# Inverter_New.net
KiCad netlist of a schematic drawn in EAGLE
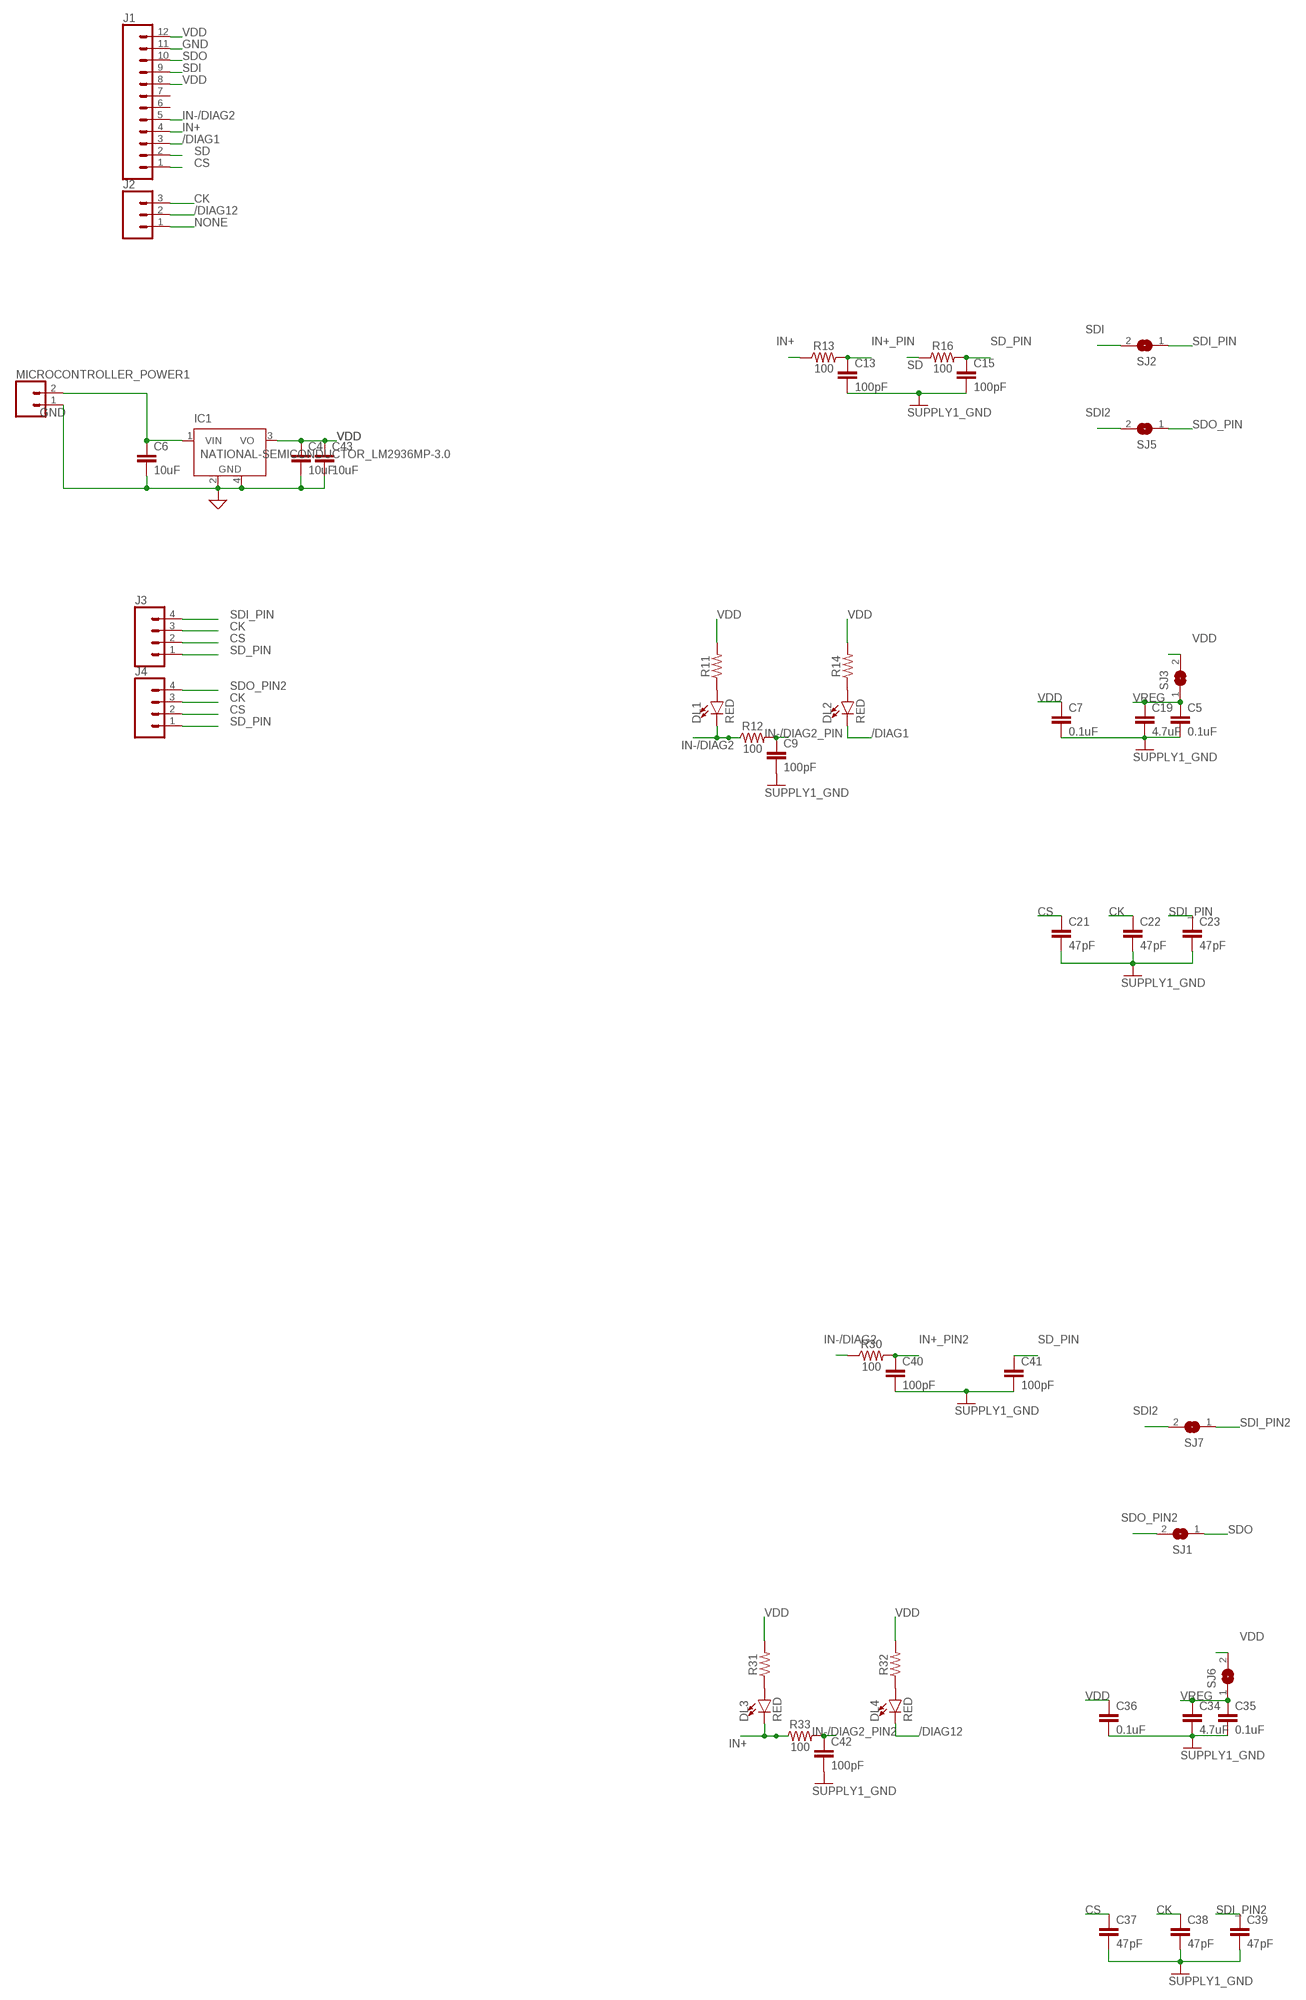
[diagram p0: schematic, sheet 1, part 1 of 2]
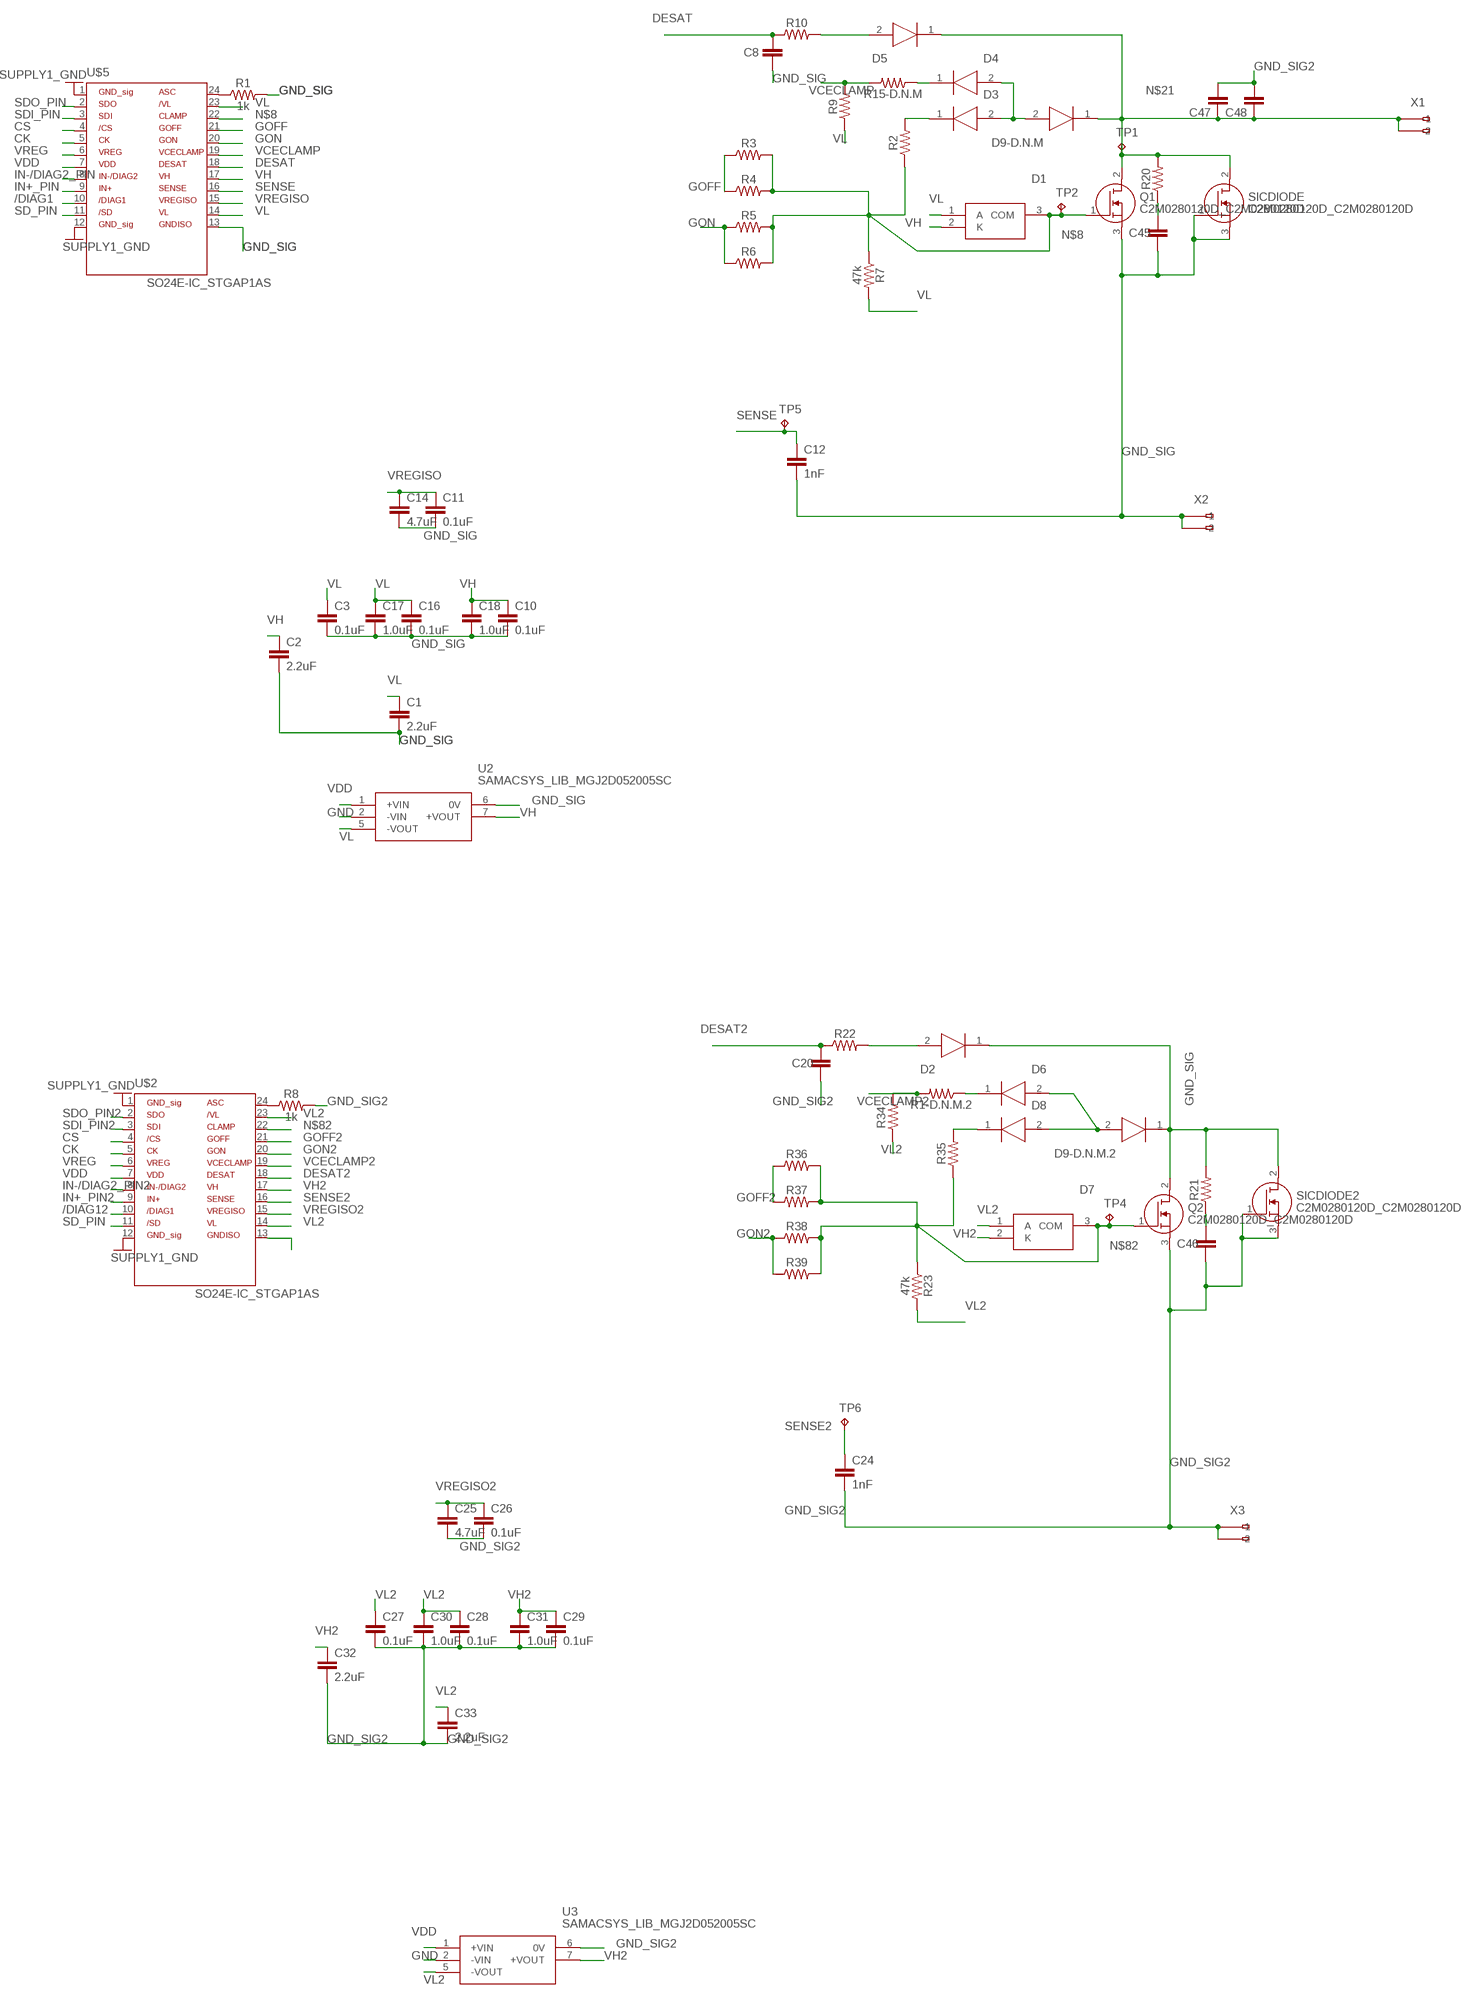
[diagram p1: schematic, sheet 1, part 2 of 2]
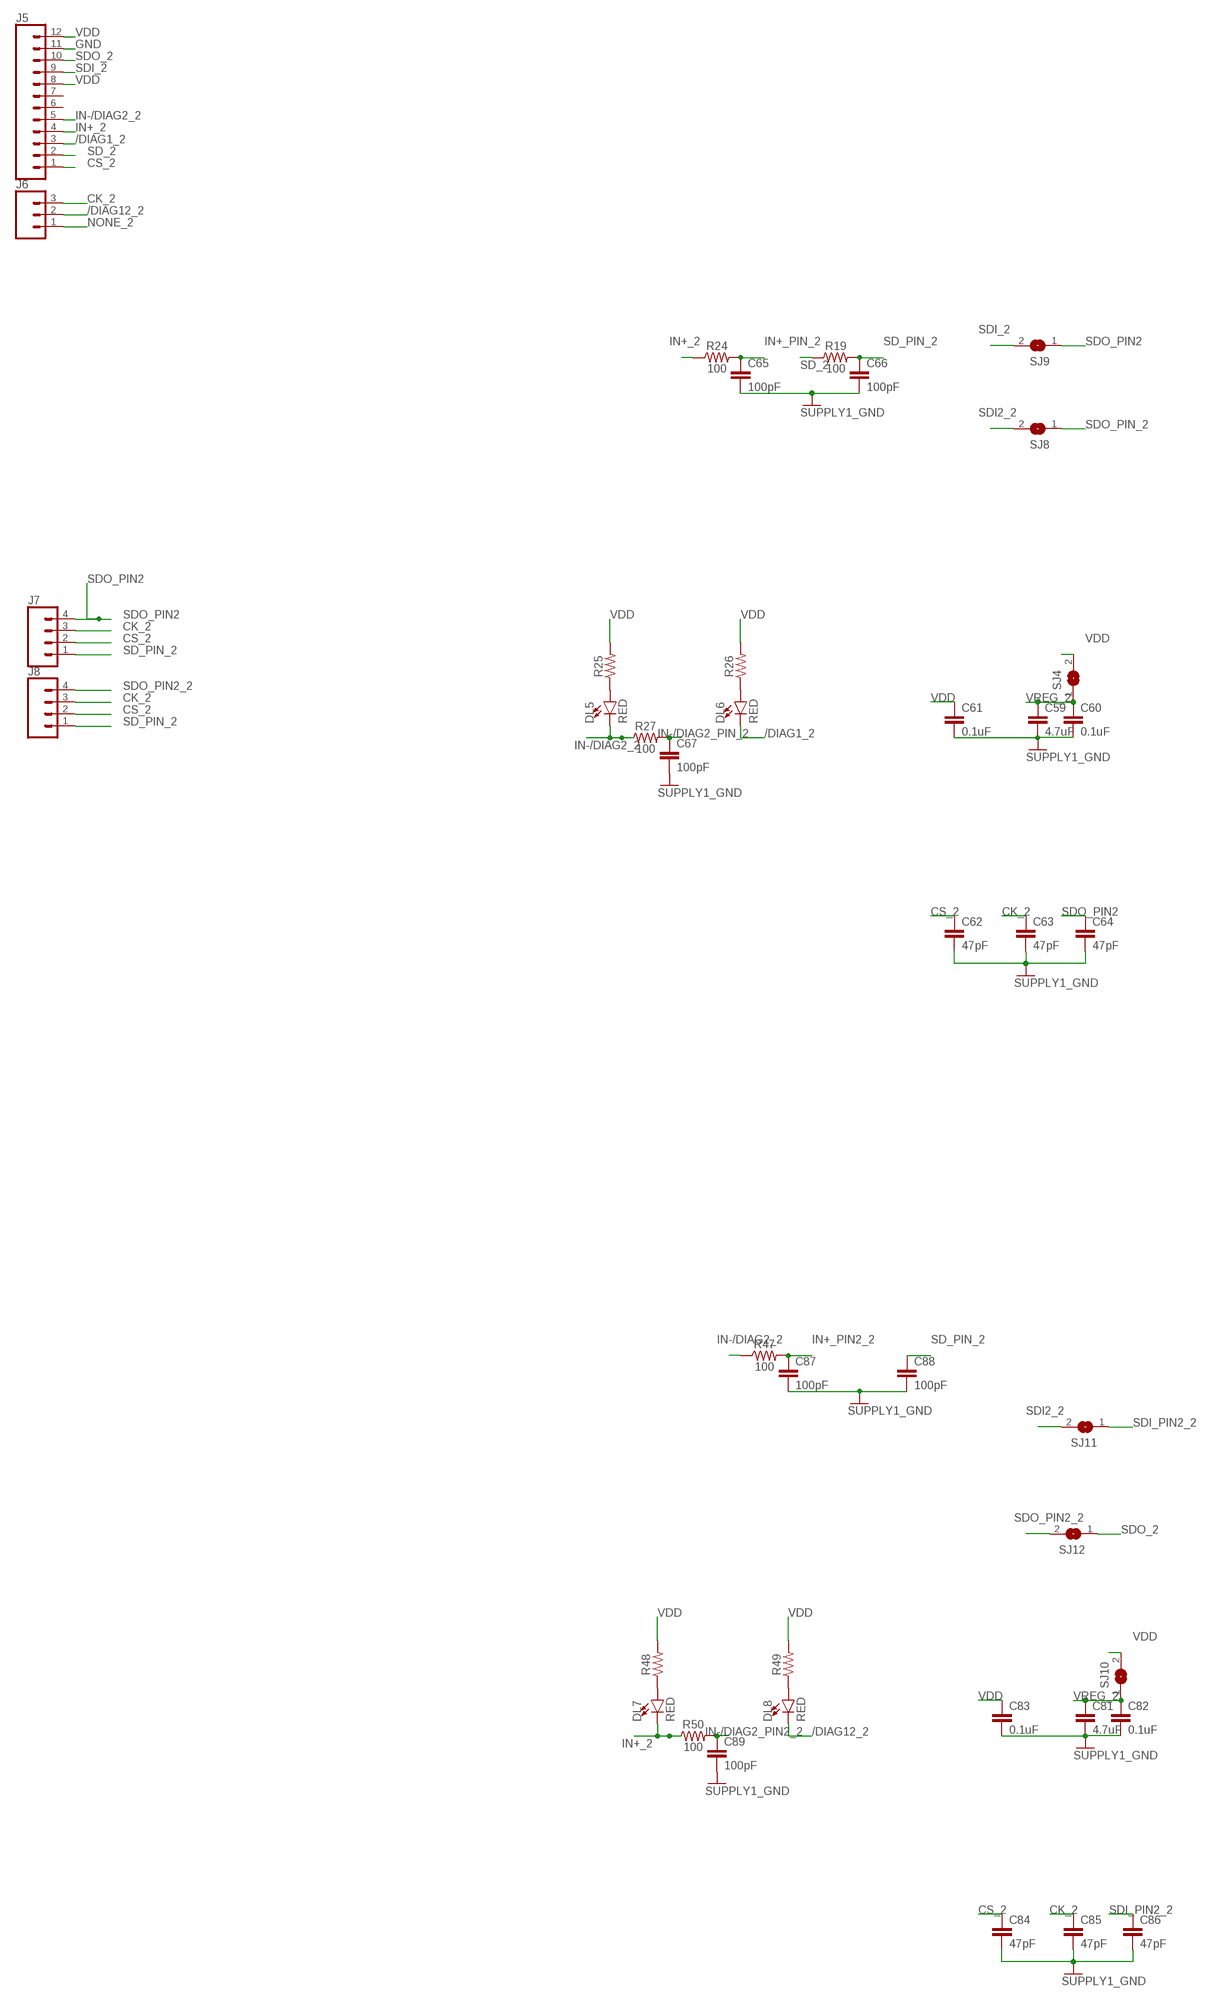
[diagram p2: schematic, sheet 2, part 1 of 2]
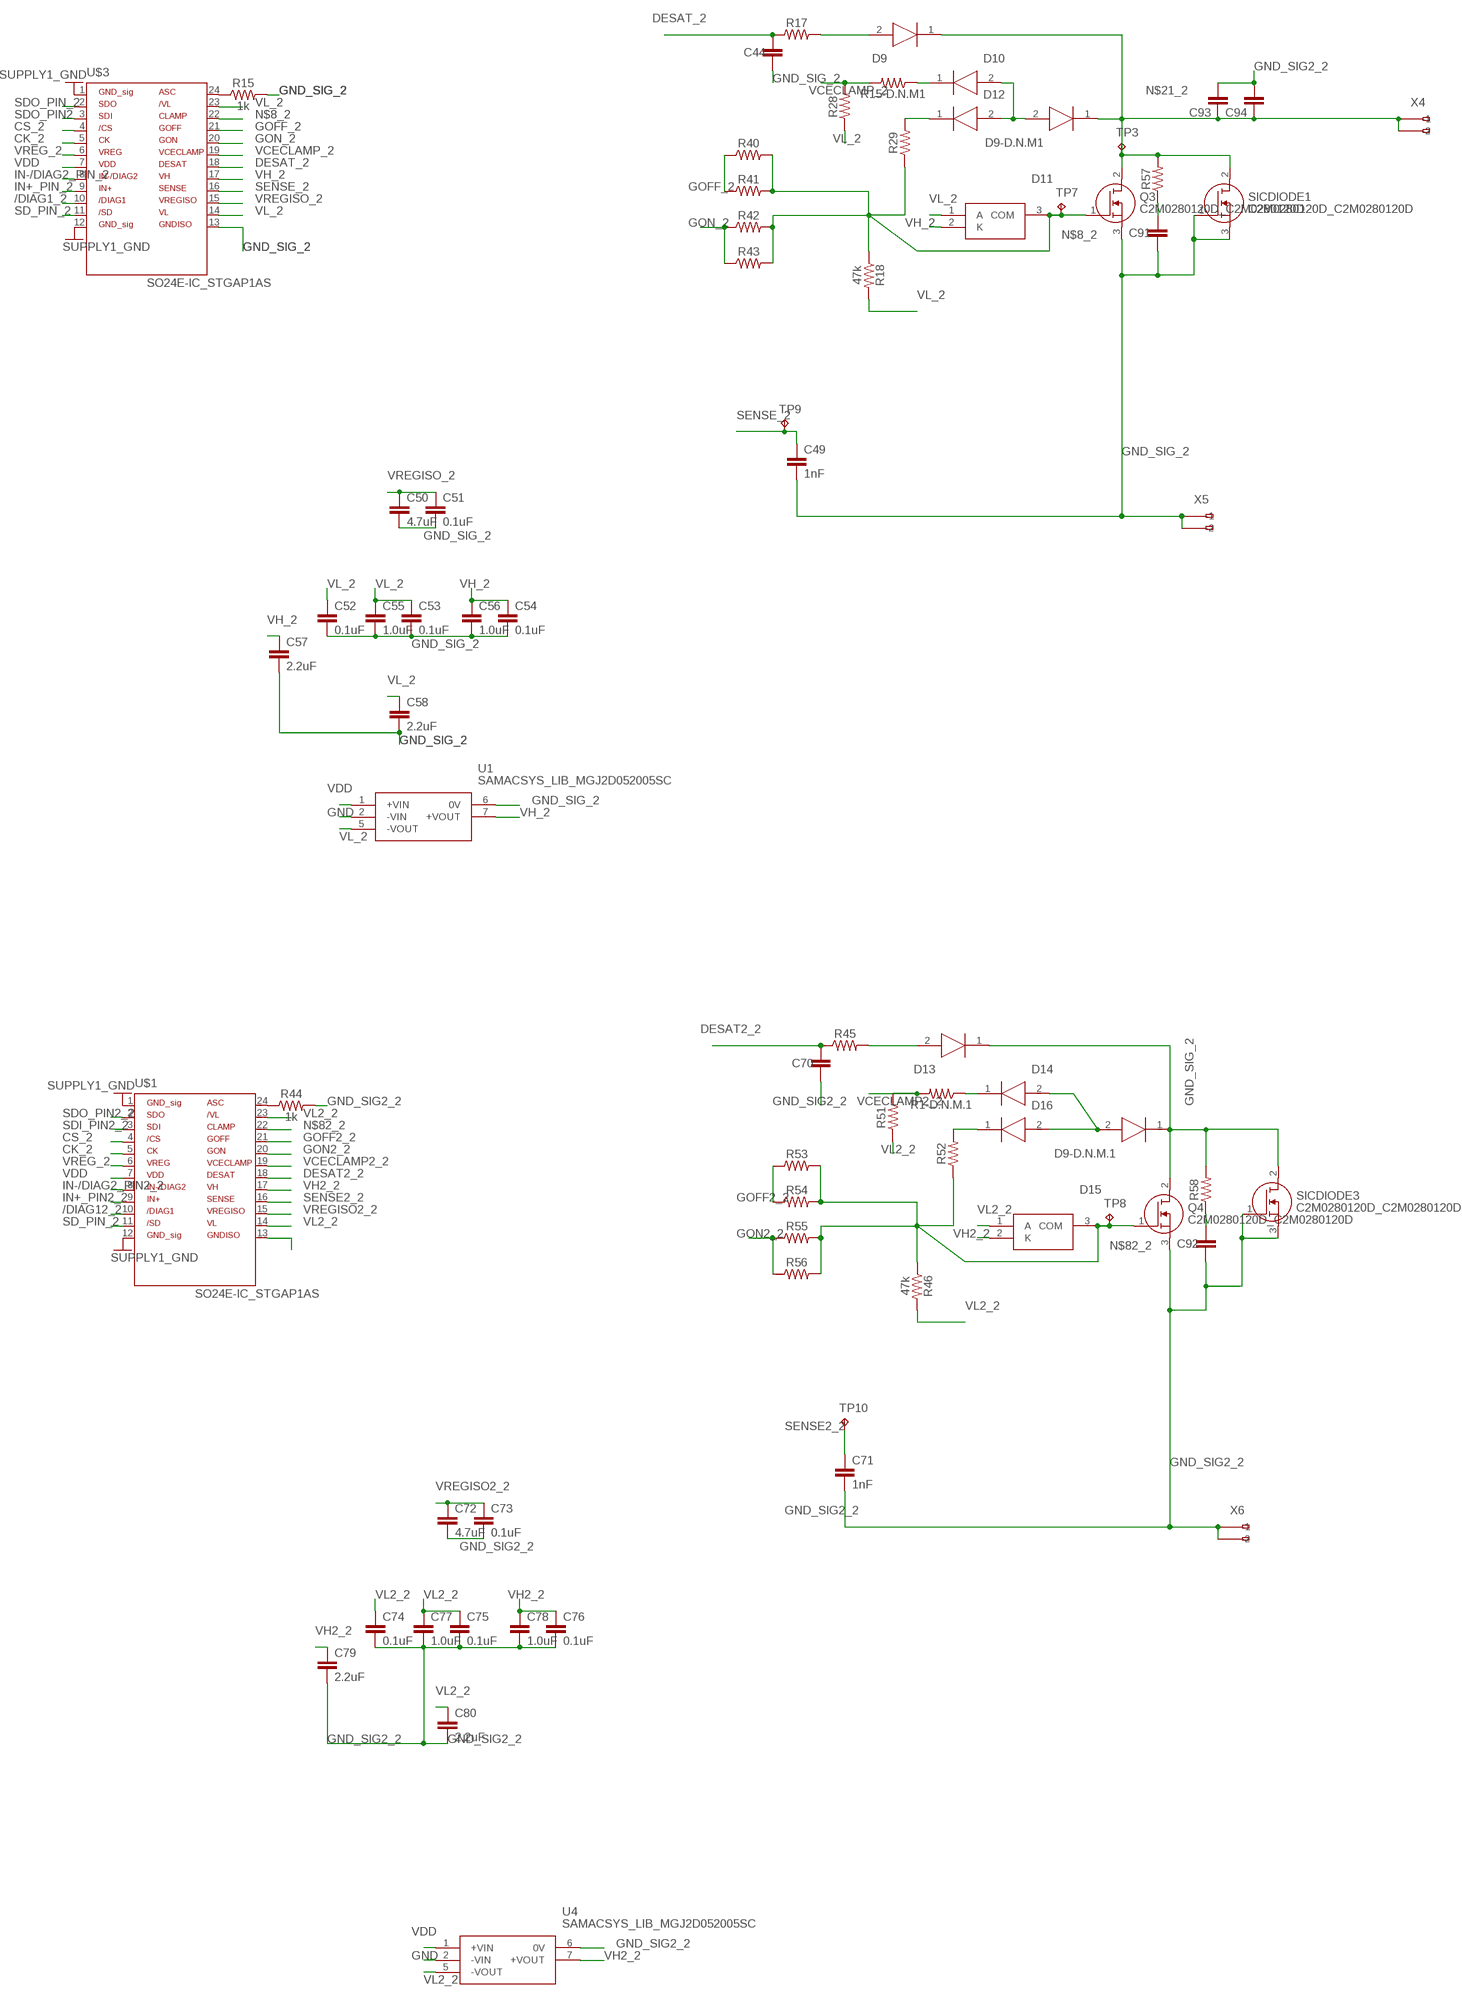
[diagram p3: schematic, sheet 2, part 2 of 2]

(export (version "E")
  (design (tool "Eeschema 10.0.6"))
  (components
    (comp (ref "C44")
      (value "100pF")
      (footprint "eagle-import:SPARKFUN-CAPACITORS_0603")
      (libsource (lib "eagle-import") (part "SPARKFUN-CAPACITORS_100PF-0603-50V-5%"))
    )
    (comp (ref "C49")
      (value "1nF")
      (footprint "eagle-import:SPARKFUN-CAPACITORS_0603")
      (libsource (lib "eagle-import") (part "SPARKFUN-CAPACITORS_1.0NF/1000PF-0603-50V-10%"))
    )
    (comp (ref "C50")
      (value "4.7uF")
      (footprint "eagle-import:SPARKFUN-CAPACITORS_0603")
      (libsource (lib "eagle-import") (part "SPARKFUN-CAPACITORS_4.7UF0603"))
    )
    (comp (ref "C51")
      (value "0.1uF")
      (footprint "eagle-import:SPARKFUN-CAPACITORS_0603")
      (libsource (lib "eagle-import") (part "SPARKFUN-CAPACITORS_0.1UF-0603-100V-10%"))
    )
    (comp (ref "C52")
      (value "0.1uF")
      (footprint "eagle-import:SPARKFUN-CAPACITORS_0603")
      (libsource (lib "eagle-import") (part "SPARKFUN-CAPACITORS_0.1UF-0603-100V-10%"))
    )
    (comp (ref "C53")
      (value "0.1uF")
      (footprint "eagle-import:SPARKFUN-CAPACITORS_0603")
      (libsource (lib "eagle-import") (part "SPARKFUN-CAPACITORS_0.1UF-0603-100V-10%"))
    )
    (comp (ref "C54")
      (value "0.1uF")
      (footprint "eagle-import:SPARKFUN-CAPACITORS_0603")
      (libsource (lib "eagle-import") (part "SPARKFUN-CAPACITORS_0.1UF-0603-100V-10%"))
    )
    (comp (ref "C55")
      (value "1.0uF")
      (footprint "eagle-import:SPARKFUN-CAPACITORS_0805")
      (libsource (lib "eagle-import") (part "SPARKFUN-CAPACITORS_1.0UF-0805-25V-10%"))
    )
    (comp (ref "C56")
      (value "1.0uF")
      (footprint "eagle-import:SPARKFUN-CAPACITORS_0805")
      (libsource (lib "eagle-import") (part "SPARKFUN-CAPACITORS_1.0UF-0805-25V-10%"))
    )
    (comp (ref "C57")
      (value "2.2uF")
      (footprint "eagle-import:SPARKFUN-CAPACITORS_1206")
      (libsource (lib "eagle-import") (part "SPARKFUN-CAPACITORS_2.2UF-1206-50V-10%"))
    )
    (comp (ref "C58")
      (value "2.2uF")
      (footprint "eagle-import:SPARKFUN-CAPACITORS_1206")
      (libsource (lib "eagle-import") (part "SPARKFUN-CAPACITORS_2.2UF-1206-50V-10%"))
    )
    (comp (ref "C59")
      (value "4.7uF")
      (footprint "eagle-import:SPARKFUN-CAPACITORS_0603")
      (libsource (lib "eagle-import") (part "SPARKFUN-CAPACITORS_4.7UF0603"))
    )
    (comp (ref "C60")
      (value "0.1uF")
      (footprint "eagle-import:SPARKFUN-CAPACITORS_0603")
      (libsource (lib "eagle-import") (part "SPARKFUN-CAPACITORS_0.1UF-0603-100V-10%"))
    )
    (comp (ref "C61")
      (value "0.1uF")
      (footprint "eagle-import:SPARKFUN-CAPACITORS_0603")
      (libsource (lib "eagle-import") (part "SPARKFUN-CAPACITORS_0.1UF-0603-100V-10%"))
    )
    (comp (ref "C62")
      (value "47pF")
      (footprint "eagle-import:SPARKFUN-CAPACITORS_0603")
      (libsource (lib "eagle-import") (part "SPARKFUN-CAPACITORS_47PF-0603-50V-5%"))
    )
    (comp (ref "C63")
      (value "47pF")
      (footprint "eagle-import:SPARKFUN-CAPACITORS_0603")
      (libsource (lib "eagle-import") (part "SPARKFUN-CAPACITORS_47PF-0603-50V-5%"))
    )
    (comp (ref "C64")
      (value "47pF")
      (footprint "eagle-import:SPARKFUN-CAPACITORS_0603")
      (libsource (lib "eagle-import") (part "SPARKFUN-CAPACITORS_47PF-0603-50V-5%"))
    )
    (comp (ref "C65")
      (value "100pF")
      (footprint "eagle-import:SPARKFUN-CAPACITORS_0603")
      (libsource (lib "eagle-import") (part "SPARKFUN-CAPACITORS_100PF-0603-50V-5%"))
    )
    (comp (ref "C66")
      (value "100pF")
      (footprint "eagle-import:SPARKFUN-CAPACITORS_0603")
      (libsource (lib "eagle-import") (part "SPARKFUN-CAPACITORS_100PF-0603-50V-5%"))
    )
    (comp (ref "C67")
      (value "100pF")
      (footprint "eagle-import:SPARKFUN-CAPACITORS_0603")
      (libsource (lib "eagle-import") (part "SPARKFUN-CAPACITORS_100PF-0603-50V-5%"))
    )
    (comp (ref "C70")
      (value "100pF")
      (footprint "eagle-import:SPARKFUN-CAPACITORS_0603")
      (libsource (lib "eagle-import") (part "SPARKFUN-CAPACITORS_100PF-0603-50V-5%"))
    )
    (comp (ref "C71")
      (value "1nF")
      (footprint "eagle-import:SPARKFUN-CAPACITORS_0603")
      (libsource (lib "eagle-import") (part "SPARKFUN-CAPACITORS_1.0NF/1000PF-0603-50V-10%"))
    )
    (comp (ref "C72")
      (value "4.7uF")
      (footprint "eagle-import:SPARKFUN-CAPACITORS_0603")
      (libsource (lib "eagle-import") (part "SPARKFUN-CAPACITORS_4.7UF0603"))
    )
    (comp (ref "C73")
      (value "0.1uF")
      (footprint "eagle-import:SPARKFUN-CAPACITORS_0603")
      (libsource (lib "eagle-import") (part "SPARKFUN-CAPACITORS_0.1UF-0603-100V-10%"))
    )
    (comp (ref "C74")
      (value "0.1uF")
      (footprint "eagle-import:SPARKFUN-CAPACITORS_0603")
      (libsource (lib "eagle-import") (part "SPARKFUN-CAPACITORS_0.1UF-0603-100V-10%"))
    )
    (comp (ref "C75")
      (value "0.1uF")
      (footprint "eagle-import:SPARKFUN-CAPACITORS_0603")
      (libsource (lib "eagle-import") (part "SPARKFUN-CAPACITORS_0.1UF-0603-100V-10%"))
    )
    (comp (ref "C76")
      (value "0.1uF")
      (footprint "eagle-import:SPARKFUN-CAPACITORS_0603")
      (libsource (lib "eagle-import") (part "SPARKFUN-CAPACITORS_0.1UF-0603-100V-10%"))
    )
    (comp (ref "C77")
      (value "1.0uF")
      (footprint "eagle-import:SPARKFUN-CAPACITORS_0805")
      (libsource (lib "eagle-import") (part "SPARKFUN-CAPACITORS_1.0UF-0805-25V-10%"))
    )
    (comp (ref "C78")
      (value "1.0uF")
      (footprint "eagle-import:SPARKFUN-CAPACITORS_0805")
      (libsource (lib "eagle-import") (part "SPARKFUN-CAPACITORS_1.0UF-0805-25V-10%"))
    )
    (comp (ref "C79")
      (value "2.2uF")
      (footprint "eagle-import:SPARKFUN-CAPACITORS_1206")
      (fields (field (name "SPICEPREFIX") "C"))
      (libsource (lib "eagle-import") (part "SPARKFUN-CAPACITORS_2.2UF-1206-50V-10%"))
    )
    (comp (ref "C80")
      (value "2.2uF")
      (footprint "eagle-import:SPARKFUN-CAPACITORS_1206")
      (libsource (lib "eagle-import") (part "SPARKFUN-CAPACITORS_2.2UF-1206-50V-10%"))
    )
    (comp (ref "C81")
      (value "4.7uF")
      (footprint "eagle-import:SPARKFUN-CAPACITORS_0603")
      (libsource (lib "eagle-import") (part "SPARKFUN-CAPACITORS_4.7UF0603"))
    )
    (comp (ref "C82")
      (value "0.1uF")
      (footprint "eagle-import:SPARKFUN-CAPACITORS_0603")
      (libsource (lib "eagle-import") (part "SPARKFUN-CAPACITORS_0.1UF-0603-100V-10%"))
    )
    (comp (ref "C83")
      (value "0.1uF")
      (footprint "eagle-import:SPARKFUN-CAPACITORS_0603")
      (libsource (lib "eagle-import") (part "SPARKFUN-CAPACITORS_0.1UF-0603-100V-10%"))
    )
    (comp (ref "C84")
      (value "47pF")
      (footprint "eagle-import:SPARKFUN-CAPACITORS_0603")
      (libsource (lib "eagle-import") (part "SPARKFUN-CAPACITORS_47PF-0603-50V-5%"))
    )
    (comp (ref "C85")
      (value "47pF")
      (footprint "eagle-import:SPARKFUN-CAPACITORS_0603")
      (libsource (lib "eagle-import") (part "SPARKFUN-CAPACITORS_47PF-0603-50V-5%"))
    )
    (comp (ref "C86")
      (value "47pF")
      (footprint "eagle-import:SPARKFUN-CAPACITORS_0603")
      (libsource (lib "eagle-import") (part "SPARKFUN-CAPACITORS_47PF-0603-50V-5%"))
    )
    (comp (ref "C87")
      (value "100pF")
      (footprint "eagle-import:SPARKFUN-CAPACITORS_0603")
      (libsource (lib "eagle-import") (part "SPARKFUN-CAPACITORS_100PF-0603-50V-5%"))
    )
    (comp (ref "C88")
      (value "100pF")
      (footprint "eagle-import:SPARKFUN-CAPACITORS_0603")
      (libsource (lib "eagle-import") (part "SPARKFUN-CAPACITORS_100PF-0603-50V-5%"))
    )
    (comp (ref "C89")
      (value "100pF")
      (footprint "eagle-import:SPARKFUN-CAPACITORS_0603")
      (libsource (lib "eagle-import") (part "SPARKFUN-CAPACITORS_100PF-0603-50V-5%"))
    )
    (comp (ref "C91")
      (value "100pF")
      (footprint "eagle-import:SPARKFUN-CAPACITORS_0603")
      (libsource (lib "eagle-import") (part "SPARKFUN-CAPACITORS_100PF-0603-50V-5%"))
    )
    (comp (ref "C92")
      (value "100pF")
      (footprint "eagle-import:SPARKFUN-CAPACITORS_0603")
      (libsource (lib "eagle-import") (part "SPARKFUN-CAPACITORS_100PF-0603-50V-5%"))
    )
    (comp (ref "C93")
      (value "C-EU225-062X268")
      (footprint "eagle-import:C225-062X268")
      (libsource (lib "eagle-import") (part "C-EU225-062X268"))
    )
    (comp (ref "C94")
      (value "C-EU225-062X268")
      (footprint "eagle-import:C225-062X268")
      (libsource (lib "eagle-import") (part "C-EU225-062X268"))
    )
    (comp (ref "D9")
      (value "STTH112A_STTH112A")
      (footprint "eagle-import:STTH112A_DIOM5126X265N")
      (fields (field (name "MANUFACTURER_PART_NUMBER") "STTH112A") (field (name "RS_PART_NUMBER") "0249319"))
      (libsource (lib "eagle-import") (part "STTH112A_STTH112A"))
    )
    (comp (ref "D9-D.N.M.1")
      (value "STPS2H100A_STPS2H100A")
      (footprint "eagle-import:STPS2H100A_DIOM5126X265N")
      (fields
        (field (name "MANUFACTURER_PART_NUMBER") "STPS2H100A")
        (field (name "RS_PART_NUMBER") "0249612P")
        (field (name "SPICEPREFIX") "D")
      )
      (libsource (lib "eagle-import") (part "STPS2H100A_STPS2H100A"))
    )
    (comp (ref "D9-D.N.M1")
      (value "STPS2H100A_STPS2H100A")
      (footprint "eagle-import:STPS2H100A_DIOM5126X265N")
      (fields
        (field (name "MANUFACTURER_PART_NUMBER") "STPS2H100A")
        (field (name "RS_PART_NUMBER") "0249612P")
      )
      (libsource (lib "eagle-import") (part "STPS2H100A_STPS2H100A"))
    )
    (comp (ref "D10")
      (value "BAT20JFILM_BAT20JFILM")
      (footprint "eagle-import:BAT20JFILM_SOD2512X113N")
      (fields
        (field (name "MANUFACTURER_PART_NUMBER") "BAT20JFILM")
        (field (name "RS_PART_NUMBER") "1657545")
      )
      (libsource (lib "eagle-import") (part "BAT20JFILM_BAT20JFILM"))
    )
    (comp (ref "D11")
      (value "BAT54SFILM_BAT54SFILM")
      (footprint "eagle-import:BAT54SFILM_SOT105P242X150-3N")
      (fields
        (field (name "MANUFACTURER_PART_NUMBER") "BAT54SFILM")
        (field (name "RS_PART_NUMBER") "7146863P")
      )
      (libsource (lib "eagle-import") (part "BAT54SFILM_BAT54SFILM"))
    )
    (comp (ref "D12")
      (value "STPS2H100A_STPS2H100A")
      (footprint "eagle-import:STPS2H100A_DIOM5126X265N")
      (fields
        (field (name "MANUFACTURER_PART_NUMBER") "STPS2H100A")
        (field (name "RS_PART_NUMBER") "0249612P")
      )
      (libsource (lib "eagle-import") (part "STPS2H100A_STPS2H100A"))
    )
    (comp (ref "D13")
      (value "STTH112A_STTH112A")
      (footprint "eagle-import:STTH112A_DIOM5126X265N")
      (fields (field (name "MANUFACTURER_PART_NUMBER") "STTH112A") (field (name "RS_PART_NUMBER") "0249319"))
      (libsource (lib "eagle-import") (part "STTH112A_STTH112A"))
    )
    (comp (ref "D14")
      (value "BAT20JFILM_BAT20JFILM")
      (footprint "eagle-import:BAT20JFILM_SOD2512X113N")
      (fields
        (field (name "MANUFACTURER_PART_NUMBER") "BAT20JFILM")
        (field (name "RS_PART_NUMBER") "1657545")
      )
      (libsource (lib "eagle-import") (part "BAT20JFILM_BAT20JFILM"))
    )
    (comp (ref "D15")
      (value "BAT54SFILM_BAT54SFILM")
      (footprint "eagle-import:BAT54SFILM_SOT105P242X150-3N")
      (fields
        (field (name "MANUFACTURER_PART_NUMBER") "BAT54SFILM")
        (field (name "RS_PART_NUMBER") "7146863P")
        (field (name "SPICEPREFIX") "J")
      )
      (libsource (lib "eagle-import") (part "BAT54SFILM_BAT54SFILM"))
    )
    (comp (ref "D16")
      (value "STPS2H100A_STPS2H100A")
      (footprint "eagle-import:STPS2H100A_DIOM5126X265N")
      (fields
        (field (name "MANUFACTURER_PART_NUMBER") "STPS2H100A")
        (field (name "RS_PART_NUMBER") "0249612P")
        (field (name "SPICEPREFIX") "D")
      )
      (libsource (lib "eagle-import") (part "STPS2H100A_STPS2H100A"))
    )
    (comp (ref "DL5")
      (value "RED")
      (footprint "eagle-import:SPARKFUN-LED_LED-1206")
      (libsource (lib "eagle-import") (part "SPARKFUN-LED_LED-RED1206"))
    )
    (comp (ref "DL6")
      (value "RED")
      (footprint "eagle-import:SPARKFUN-LED_LED-1206")
      (libsource (lib "eagle-import") (part "SPARKFUN-LED_LED-RED1206"))
    )
    (comp (ref "DL7")
      (value "RED")
      (footprint "eagle-import:SPARKFUN-LED_LED-1206")
      (libsource (lib "eagle-import") (part "SPARKFUN-LED_LED-RED1206"))
    )
    (comp (ref "DL8")
      (value "RED")
      (footprint "eagle-import:SPARKFUN-LED_LED-1206")
      (libsource (lib "eagle-import") (part "SPARKFUN-LED_LED-RED1206"))
    )
    (comp (ref "J5")
      (value "SPARKFUN-CONNECTORS_CONN_12LONGPADS")
      (footprint "eagle-import:SPARKFUN-CONNECTORS_1X12_LONGPADS")
      (libsource (lib "eagle-import") (part "SPARKFUN-CONNECTORS_CONN_12LONGPADS"))
    )
    (comp (ref "J6")
      (value "SPARKFUN-CONNECTORS_CONN_03LONGPADS")
      (footprint "eagle-import:SPARKFUN-CONNECTORS_1X03_LONGPADS")
      (libsource (lib "eagle-import") (part "SPARKFUN-CONNECTORS_CONN_03LONGPADS"))
    )
    (comp (ref "J7")
      (value "SPARKFUN-CONNECTORS_CONN_04LONGPADS")
      (footprint "eagle-import:SPARKFUN-CONNECTORS_1X04_LONGPADS")
      (libsource (lib "eagle-import") (part "SPARKFUN-CONNECTORS_CONN_04LONGPADS"))
    )
    (comp (ref "J8")
      (value "SPARKFUN-CONNECTORS_CONN_04LONGPADS")
      (footprint "eagle-import:SPARKFUN-CONNECTORS_1X04_LONGPADS")
      (libsource (lib "eagle-import") (part "SPARKFUN-CONNECTORS_CONN_04LONGPADS"))
    )
    (comp (ref "Q3")
      (value "C2M0280120D_C2M0280120D")
      (footprint "eagle-import:C2M0280120D_TO544P521X1594X2550-3P")
      (fields
        (field (name "MANUFACTURER_PART_NUMBER") "C2M0280120D")
        (field (name "RS_PART_NUMBER") "9158820P")
      )
      (libsource (lib "eagle-import") (part "C2M0280120D_C2M0280120D"))
    )
    (comp (ref "Q4")
      (value "C2M0280120D_C2M0280120D")
      (footprint "eagle-import:C2M0280120D_TO544P521X1594X2550-3P")
      (fields
        (field (name "MANUFACTURER_PART_NUMBER") "C2M0280120D")
        (field (name "RS_PART_NUMBER") "9158820P")
      )
      (libsource (lib "eagle-import") (part "C2M0280120D_C2M0280120D"))
    )
    (comp (ref "R1-D.N.M.1")
      (value "0")
      (footprint "eagle-import:SPARKFUN-RESISTORS_0603")
      (libsource (lib "eagle-import") (part "SPARKFUN-RESISTORS_0OHM-0603-1/10W-5%"))
    )
    (comp (ref "R15")
      (value "1k")
      (footprint "eagle-import:SPARKFUN-RESISTORS_0603")
      (libsource (lib "eagle-import") (part "SPARKFUN-RESISTORS_1KOHM-0603-1/10W-1%"))
    )
    (comp (ref "R15-D.N.M1")
      (value "0")
      (footprint "eagle-import:SPARKFUN-RESISTORS_0603")
      (libsource (lib "eagle-import") (part "SPARKFUN-RESISTORS_0OHM-0603-1/10W-5%"))
    )
    (comp (ref "R17")
      (value "1k")
      (footprint "eagle-import:SPARKFUN-RESISTORS_0603")
      (libsource (lib "eagle-import") (part "SPARKFUN-RESISTORS_1KOHM-0603-1/10W-1%"))
    )
    (comp (ref "R18")
      (value "47k")
      (footprint "eagle-import:SPARKFUN-RESISTORS_0603")
      (libsource (lib "eagle-import") (part "SPARKFUN-RESISTORS_47KOHM-0603-1/10W-1%"))
    )
    (comp (ref "R19")
      (value "100")
      (footprint "eagle-import:SPARKFUN-RESISTORS_0603")
      (libsource (lib "eagle-import") (part "SPARKFUN-RESISTORS_100OHM-0603-1/4W-5%"))
    )
    (comp (ref "R24")
      (value "100")
      (footprint "eagle-import:SPARKFUN-RESISTORS_0603")
      (libsource (lib "eagle-import") (part "SPARKFUN-RESISTORS_100OHM-0603-1/4W-5%"))
    )
    (comp (ref "R25")
      (value "SPARKFUN-RESISTORS_RESISTOR0603")
      (footprint "eagle-import:SPARKFUN-RESISTORS_0603")
      (libsource (lib "eagle-import") (part "SPARKFUN-RESISTORS_RESISTOR0603"))
    )
    (comp (ref "R26")
      (value "SPARKFUN-RESISTORS_RESISTOR0603")
      (footprint "eagle-import:SPARKFUN-RESISTORS_0603")
      (libsource (lib "eagle-import") (part "SPARKFUN-RESISTORS_RESISTOR0603"))
    )
    (comp (ref "R27")
      (value "100")
      (footprint "eagle-import:SPARKFUN-RESISTORS_0603")
      (libsource (lib "eagle-import") (part "SPARKFUN-RESISTORS_100OHM-0603-1/4W-5%"))
    )
    (comp (ref "R28")
      (value "0")
      (footprint "eagle-import:SPARKFUN-RESISTORS_0603")
      (libsource (lib "eagle-import") (part "SPARKFUN-RESISTORS_0OHM-0603-1/10W-5%"))
    )
    (comp (ref "R29")
      (value "SPARKFUN-RESISTORS_RESISTOR0805")
      (footprint "eagle-import:SPARKFUN-RESISTORS_0805")
      (libsource (lib "eagle-import") (part "SPARKFUN-RESISTORS_RESISTOR0805"))
    )
    (comp (ref "R40")
      (value "SPARKFUN-RESISTORS_RESISTOR1206")
      (footprint "eagle-import:SPARKFUN-RESISTORS_1206")
      (libsource (lib "eagle-import") (part "SPARKFUN-RESISTORS_RESISTOR1206"))
    )
    (comp (ref "R41")
      (value "SPARKFUN-RESISTORS_RESISTOR1206")
      (footprint "eagle-import:SPARKFUN-RESISTORS_1206")
      (libsource (lib "eagle-import") (part "SPARKFUN-RESISTORS_RESISTOR1206"))
    )
    (comp (ref "R42")
      (value "SPARKFUN-RESISTORS_RESISTOR1206")
      (footprint "eagle-import:SPARKFUN-RESISTORS_1206")
      (libsource (lib "eagle-import") (part "SPARKFUN-RESISTORS_RESISTOR1206"))
    )
    (comp (ref "R43")
      (value "SPARKFUN-RESISTORS_RESISTOR1206")
      (footprint "eagle-import:SPARKFUN-RESISTORS_1206")
      (libsource (lib "eagle-import") (part "SPARKFUN-RESISTORS_RESISTOR1206"))
    )
    (comp (ref "R44")
      (value "1k")
      (footprint "eagle-import:SPARKFUN-RESISTORS_0603")
      (libsource (lib "eagle-import") (part "SPARKFUN-RESISTORS_1KOHM-0603-1/10W-1%"))
    )
    (comp (ref "R45")
      (value "1k")
      (footprint "eagle-import:SPARKFUN-RESISTORS_0603")
      (libsource (lib "eagle-import") (part "SPARKFUN-RESISTORS_1KOHM-0603-1/10W-1%"))
    )
    (comp (ref "R46")
      (value "47k")
      (footprint "eagle-import:SPARKFUN-RESISTORS_0603")
      (libsource (lib "eagle-import") (part "SPARKFUN-RESISTORS_47KOHM-0603-1/10W-1%"))
    )
    (comp (ref "R47")
      (value "100")
      (footprint "eagle-import:SPARKFUN-RESISTORS_0603")
      (libsource (lib "eagle-import") (part "SPARKFUN-RESISTORS_100OHM-0603-1/4W-5%"))
    )
    (comp (ref "R48")
      (value "SPARKFUN-RESISTORS_RESISTOR0603")
      (footprint "eagle-import:SPARKFUN-RESISTORS_0603")
      (libsource (lib "eagle-import") (part "SPARKFUN-RESISTORS_RESISTOR0603"))
    )
    (comp (ref "R49")
      (value "SPARKFUN-RESISTORS_RESISTOR0603")
      (footprint "eagle-import:SPARKFUN-RESISTORS_0603")
      (libsource (lib "eagle-import") (part "SPARKFUN-RESISTORS_RESISTOR0603"))
    )
    (comp (ref "R50")
      (value "100")
      (footprint "eagle-import:SPARKFUN-RESISTORS_0603")
      (libsource (lib "eagle-import") (part "SPARKFUN-RESISTORS_100OHM-0603-1/4W-5%"))
    )
    (comp (ref "R51")
      (value "0")
      (footprint "eagle-import:SPARKFUN-RESISTORS_0603")
      (libsource (lib "eagle-import") (part "SPARKFUN-RESISTORS_0OHM-0603-1/10W-5%"))
    )
    (comp (ref "R52")
      (value "SPARKFUN-RESISTORS_RESISTOR0805")
      (footprint "eagle-import:SPARKFUN-RESISTORS_0805")
      (libsource (lib "eagle-import") (part "SPARKFUN-RESISTORS_RESISTOR0805"))
    )
    (comp (ref "R53")
      (value "SPARKFUN-RESISTORS_RESISTOR1206")
      (footprint "eagle-import:SPARKFUN-RESISTORS_1206")
      (libsource (lib "eagle-import") (part "SPARKFUN-RESISTORS_RESISTOR1206"))
    )
    (comp (ref "R54")
      (value "SPARKFUN-RESISTORS_RESISTOR1206")
      (footprint "eagle-import:SPARKFUN-RESISTORS_1206")
      (libsource (lib "eagle-import") (part "SPARKFUN-RESISTORS_RESISTOR1206"))
    )
    (comp (ref "R55")
      (value "SPARKFUN-RESISTORS_RESISTOR1206")
      (footprint "eagle-import:SPARKFUN-RESISTORS_1206")
      (libsource (lib "eagle-import") (part "SPARKFUN-RESISTORS_RESISTOR1206"))
    )
    (comp (ref "R56")
      (value "SPARKFUN-RESISTORS_RESISTOR1206")
      (footprint "eagle-import:SPARKFUN-RESISTORS_1206")
      (libsource (lib "eagle-import") (part "SPARKFUN-RESISTORS_RESISTOR1206"))
    )
    (comp (ref "R57")
      (value "SPARKFUN-RESISTORS_RESISTOR1206")
      (footprint "eagle-import:SPARKFUN-RESISTORS_1206")
      (libsource (lib "eagle-import") (part "SPARKFUN-RESISTORS_RESISTOR1206"))
    )
    (comp (ref "R58")
      (value "SPARKFUN-RESISTORS_RESISTOR1206")
      (footprint "eagle-import:SPARKFUN-RESISTORS_1206")
      (libsource (lib "eagle-import") (part "SPARKFUN-RESISTORS_RESISTOR1206"))
    )
    (comp (ref "SICDIODE1")
      (value "C2M0280120D_C2M0280120D")
      (footprint "eagle-import:C2M0280120D_TO544P521X1594X2550-3P")
      (fields
        (field (name "MANUFACTURER_PART_NUMBER") "C2M0280120D")
        (field (name "RS_PART_NUMBER") "9158820P")
      )
      (libsource (lib "eagle-import") (part "C2M0280120D_C2M0280120D"))
    )
    (comp (ref "SICDIODE3")
      (value "C2M0280120D_C2M0280120D")
      (footprint "eagle-import:C2M0280120D_TO544P521X1594X2550-3P")
      (fields
        (field (name "MANUFACTURER_PART_NUMBER") "C2M0280120D")
        (field (name "RS_PART_NUMBER") "9158820P")
      )
      (libsource (lib "eagle-import") (part "C2M0280120D_C2M0280120D"))
    )
    (comp (ref "SJ4")
      (value "JUMPER_SJ")
      (footprint "eagle-import:JUMPER_SJ")
      (libsource (lib "eagle-import") (part "JUMPER_SJ"))
    )
    (comp (ref "SJ8")
      (value "JUMPER_SJ")
      (footprint "eagle-import:JUMPER_SJ")
      (libsource (lib "eagle-import") (part "JUMPER_SJ"))
    )
    (comp (ref "SJ9")
      (value "JUMPER_SJ")
      (footprint "eagle-import:JUMPER_SJ")
      (libsource (lib "eagle-import") (part "JUMPER_SJ"))
    )
    (comp (ref "SJ10")
      (value "JUMPER_SJ")
      (footprint "eagle-import:JUMPER_SJ")
      (libsource (lib "eagle-import") (part "JUMPER_SJ"))
    )
    (comp (ref "SJ11")
      (value "JUMPER_SJ")
      (footprint "eagle-import:JUMPER_SJ")
      (libsource (lib "eagle-import") (part "JUMPER_SJ"))
    )
    (comp (ref "SJ12")
      (value "JUMPER_SJ")
      (footprint "eagle-import:JUMPER_SJ")
      (libsource (lib "eagle-import") (part "JUMPER_SJ"))
    )
    (comp (ref "TP3")
      (value "TPTP15SQ")
      (footprint "eagle-import:TP15SQ")
      (libsource (lib "eagle-import") (part "TPTP15SQ"))
    )
    (comp (ref "TP7")
      (value "TPTP15SQ")
      (footprint "eagle-import:TP15SQ")
      (libsource (lib "eagle-import") (part "TPTP15SQ"))
    )
    (comp (ref "TP8")
      (value "TPTP15SQ")
      (footprint "eagle-import:TP15SQ")
      (libsource (lib "eagle-import") (part "TPTP15SQ"))
    )
    (comp (ref "TP9")
      (value "TPTP15SQ")
      (footprint "eagle-import:TP15SQ")
      (libsource (lib "eagle-import") (part "TPTP15SQ"))
    )
    (comp (ref "TP10")
      (value "TPTP15SQ")
      (footprint "eagle-import:TP15SQ")
      (libsource (lib "eagle-import") (part "TPTP15SQ"))
    )
    (comp (ref "U$1")
      (value "SO24E-IC_STGAP1AS")
      (footprint "eagle-import:SO24E-IC_SO24W")
      (libsource (lib "eagle-import") (part "SO24E-IC_STGAP1AS"))
    )
    (comp (ref "U$3")
      (value "SO24E-IC_STGAP1AS")
      (footprint "eagle-import:SO24E-IC_SO24W")
      (libsource (lib "eagle-import") (part "SO24E-IC_STGAP1AS"))
    )
    (comp (ref "U1")
      (value "SAMACSYS_LIB_MGJ2D052005SC")
      (footprint "eagle-import:SAMACSYS_LIB_MGJ2D_7-PIN-SIP")
      (fields (field (name "ARROW_PART_NUMBER") "MGJ2D052005SC") (field (name "RS_PART_NUMBER") "8163506P"))
      (libsource (lib "eagle-import") (part "SAMACSYS_LIB_MGJ2D052005SC"))
    )
    (comp (ref "U4")
      (value "SAMACSYS_LIB_MGJ2D052005SC")
      (footprint "eagle-import:SAMACSYS_LIB_MGJ2D_7-PIN-SIP")
      (fields (field (name "ARROW_PART_NUMBER") "MGJ2D052005SC") (field (name "RS_PART_NUMBER") "8163506P"))
      (libsource (lib "eagle-import") (part "SAMACSYS_LIB_MGJ2D052005SC"))
    )
    (comp (ref "X4")
      (value "234-502")
      (footprint "eagle-import:234-502")
      (libsource (lib "eagle-import") (part "234-502"))
    )
    (comp (ref "X5")
      (value "234-502")
      (footprint "eagle-import:234-502")
      (libsource (lib "eagle-import") (part "234-502"))
    )
    (comp (ref "X6")
      (value "234-502")
      (footprint "eagle-import:234-502")
      (libsource (lib "eagle-import") (part "234-502"))
    )
    (comp (ref "C1")
      (value "2.2uF")
      (footprint "eagle-import:SPARKFUN-CAPACITORS_1206")
      (libsource (lib "eagle-import") (part "SPARKFUN-CAPACITORS_2.2UF-1206-50V-10%"))
    )
    (comp (ref "C2")
      (value "2.2uF")
      (footprint "eagle-import:SPARKFUN-CAPACITORS_1206")
      (libsource (lib "eagle-import") (part "SPARKFUN-CAPACITORS_2.2UF-1206-50V-10%"))
    )
    (comp (ref "C3")
      (value "0.1uF")
      (footprint "eagle-import:SPARKFUN-CAPACITORS_0603")
      (libsource (lib "eagle-import") (part "SPARKFUN-CAPACITORS_0.1UF-0603-100V-10%"))
    )
    (comp (ref "C4")
      (value "10uF")
      (footprint "eagle-import:SPARKFUN-CAPACITORS_1210")
      (libsource (lib "eagle-import") (part "SPARKFUN-CAPACITORS_10UF-1210-50V-20%"))
    )
    (comp (ref "C5")
      (value "0.1uF")
      (footprint "eagle-import:SPARKFUN-CAPACITORS_0603")
      (libsource (lib "eagle-import") (part "SPARKFUN-CAPACITORS_0.1UF-0603-100V-10%"))
    )
    (comp (ref "C6")
      (value "10uF")
      (footprint "eagle-import:SPARKFUN-CAPACITORS_1210")
      (libsource (lib "eagle-import") (part "SPARKFUN-CAPACITORS_10UF-1210-50V-20%"))
    )
    (comp (ref "C7")
      (value "0.1uF")
      (footprint "eagle-import:SPARKFUN-CAPACITORS_0603")
      (libsource (lib "eagle-import") (part "SPARKFUN-CAPACITORS_0.1UF-0603-100V-10%"))
    )
    (comp (ref "C8")
      (value "100pF")
      (footprint "eagle-import:SPARKFUN-CAPACITORS_0603")
      (libsource (lib "eagle-import") (part "SPARKFUN-CAPACITORS_100PF-0603-50V-5%"))
    )
    (comp (ref "C9")
      (value "100pF")
      (footprint "eagle-import:SPARKFUN-CAPACITORS_0603")
      (libsource (lib "eagle-import") (part "SPARKFUN-CAPACITORS_100PF-0603-50V-5%"))
    )
    (comp (ref "C10")
      (value "0.1uF")
      (footprint "eagle-import:SPARKFUN-CAPACITORS_0603")
      (libsource (lib "eagle-import") (part "SPARKFUN-CAPACITORS_0.1UF-0603-100V-10%"))
    )
    (comp (ref "C11")
      (value "0.1uF")
      (footprint "eagle-import:SPARKFUN-CAPACITORS_0603")
      (libsource (lib "eagle-import") (part "SPARKFUN-CAPACITORS_0.1UF-0603-100V-10%"))
    )
    (comp (ref "C12")
      (value "1nF")
      (footprint "eagle-import:SPARKFUN-CAPACITORS_0603")
      (libsource (lib "eagle-import") (part "SPARKFUN-CAPACITORS_1.0NF/1000PF-0603-50V-10%"))
    )
    (comp (ref "C13")
      (value "100pF")
      (footprint "eagle-import:SPARKFUN-CAPACITORS_0603")
      (libsource (lib "eagle-import") (part "SPARKFUN-CAPACITORS_100PF-0603-50V-5%"))
    )
    (comp (ref "C14")
      (value "4.7uF")
      (footprint "eagle-import:SPARKFUN-CAPACITORS_0603")
      (libsource (lib "eagle-import") (part "SPARKFUN-CAPACITORS_4.7UF0603"))
    )
    (comp (ref "C15")
      (value "100pF")
      (footprint "eagle-import:SPARKFUN-CAPACITORS_0603")
      (libsource (lib "eagle-import") (part "SPARKFUN-CAPACITORS_100PF-0603-50V-5%"))
    )
    (comp (ref "C16")
      (value "0.1uF")
      (footprint "eagle-import:SPARKFUN-CAPACITORS_0603")
      (libsource (lib "eagle-import") (part "SPARKFUN-CAPACITORS_0.1UF-0603-100V-10%"))
    )
    (comp (ref "C17")
      (value "1.0uF")
      (footprint "eagle-import:SPARKFUN-CAPACITORS_0805")
      (libsource (lib "eagle-import") (part "SPARKFUN-CAPACITORS_1.0UF-0805-25V-10%"))
    )
    (comp (ref "C18")
      (value "1.0uF")
      (footprint "eagle-import:SPARKFUN-CAPACITORS_0805")
      (libsource (lib "eagle-import") (part "SPARKFUN-CAPACITORS_1.0UF-0805-25V-10%"))
    )
    (comp (ref "C19")
      (value "4.7uF")
      (footprint "eagle-import:SPARKFUN-CAPACITORS_0603")
      (libsource (lib "eagle-import") (part "SPARKFUN-CAPACITORS_4.7UF0603"))
    )
    (comp (ref "C20")
      (value "100pF")
      (footprint "eagle-import:SPARKFUN-CAPACITORS_0603")
      (libsource (lib "eagle-import") (part "SPARKFUN-CAPACITORS_100PF-0603-50V-5%"))
    )
    (comp (ref "C21")
      (value "47pF")
      (footprint "eagle-import:SPARKFUN-CAPACITORS_0603")
      (libsource (lib "eagle-import") (part "SPARKFUN-CAPACITORS_47PF-0603-50V-5%"))
    )
    (comp (ref "C22")
      (value "47pF")
      (footprint "eagle-import:SPARKFUN-CAPACITORS_0603")
      (libsource (lib "eagle-import") (part "SPARKFUN-CAPACITORS_47PF-0603-50V-5%"))
    )
    (comp (ref "C23")
      (value "47pF")
      (footprint "eagle-import:SPARKFUN-CAPACITORS_0603")
      (libsource (lib "eagle-import") (part "SPARKFUN-CAPACITORS_47PF-0603-50V-5%"))
    )
    (comp (ref "C24")
      (value "1nF")
      (footprint "eagle-import:SPARKFUN-CAPACITORS_0603")
      (libsource (lib "eagle-import") (part "SPARKFUN-CAPACITORS_1.0NF/1000PF-0603-50V-10%"))
    )
    (comp (ref "C25")
      (value "4.7uF")
      (footprint "eagle-import:SPARKFUN-CAPACITORS_0603")
      (libsource (lib "eagle-import") (part "SPARKFUN-CAPACITORS_4.7UF0603"))
    )
    (comp (ref "C26")
      (value "0.1uF")
      (footprint "eagle-import:SPARKFUN-CAPACITORS_0603")
      (libsource (lib "eagle-import") (part "SPARKFUN-CAPACITORS_0.1UF-0603-100V-10%"))
    )
    (comp (ref "C27")
      (value "0.1uF")
      (footprint "eagle-import:SPARKFUN-CAPACITORS_0603")
      (libsource (lib "eagle-import") (part "SPARKFUN-CAPACITORS_0.1UF-0603-100V-10%"))
    )
    (comp (ref "C28")
      (value "0.1uF")
      (footprint "eagle-import:SPARKFUN-CAPACITORS_0603")
      (libsource (lib "eagle-import") (part "SPARKFUN-CAPACITORS_0.1UF-0603-100V-10%"))
    )
    (comp (ref "C29")
      (value "0.1uF")
      (footprint "eagle-import:SPARKFUN-CAPACITORS_0603")
      (libsource (lib "eagle-import") (part "SPARKFUN-CAPACITORS_0.1UF-0603-100V-10%"))
    )
    (comp (ref "C30")
      (value "1.0uF")
      (footprint "eagle-import:SPARKFUN-CAPACITORS_0805")
      (libsource (lib "eagle-import") (part "SPARKFUN-CAPACITORS_1.0UF-0805-25V-10%"))
    )
    (comp (ref "C31")
      (value "1.0uF")
      (footprint "eagle-import:SPARKFUN-CAPACITORS_0805")
      (libsource (lib "eagle-import") (part "SPARKFUN-CAPACITORS_1.0UF-0805-25V-10%"))
    )
    (comp (ref "C32")
      (value "2.2uF")
      (footprint "eagle-import:SPARKFUN-CAPACITORS_1206")
      (fields (field (name "SPICEPREFIX") "C"))
      (libsource (lib "eagle-import") (part "SPARKFUN-CAPACITORS_2.2UF-1206-50V-10%"))
    )
    (comp (ref "C33")
      (value "2.2uF")
      (footprint "eagle-import:SPARKFUN-CAPACITORS_1206")
      (libsource (lib "eagle-import") (part "SPARKFUN-CAPACITORS_2.2UF-1206-50V-10%"))
    )
    (comp (ref "C34")
      (value "4.7uF")
      (footprint "eagle-import:SPARKFUN-CAPACITORS_0603")
      (libsource (lib "eagle-import") (part "SPARKFUN-CAPACITORS_4.7UF0603"))
    )
    (comp (ref "C35")
      (value "0.1uF")
      (footprint "eagle-import:SPARKFUN-CAPACITORS_0603")
      (libsource (lib "eagle-import") (part "SPARKFUN-CAPACITORS_0.1UF-0603-100V-10%"))
    )
    (comp (ref "C36")
      (value "0.1uF")
      (footprint "eagle-import:SPARKFUN-CAPACITORS_0603")
      (libsource (lib "eagle-import") (part "SPARKFUN-CAPACITORS_0.1UF-0603-100V-10%"))
    )
    (comp (ref "C37")
      (value "47pF")
      (footprint "eagle-import:SPARKFUN-CAPACITORS_0603")
      (libsource (lib "eagle-import") (part "SPARKFUN-CAPACITORS_47PF-0603-50V-5%"))
    )
    (comp (ref "C38")
      (value "47pF")
      (footprint "eagle-import:SPARKFUN-CAPACITORS_0603")
      (libsource (lib "eagle-import") (part "SPARKFUN-CAPACITORS_47PF-0603-50V-5%"))
    )
    (comp (ref "C39")
      (value "47pF")
      (footprint "eagle-import:SPARKFUN-CAPACITORS_0603")
      (libsource (lib "eagle-import") (part "SPARKFUN-CAPACITORS_47PF-0603-50V-5%"))
    )
    (comp (ref "C40")
      (value "100pF")
      (footprint "eagle-import:SPARKFUN-CAPACITORS_0603")
      (libsource (lib "eagle-import") (part "SPARKFUN-CAPACITORS_100PF-0603-50V-5%"))
    )
    (comp (ref "C41")
      (value "100pF")
      (footprint "eagle-import:SPARKFUN-CAPACITORS_0603")
      (libsource (lib "eagle-import") (part "SPARKFUN-CAPACITORS_100PF-0603-50V-5%"))
    )
    (comp (ref "C42")
      (value "100pF")
      (footprint "eagle-import:SPARKFUN-CAPACITORS_0603")
      (libsource (lib "eagle-import") (part "SPARKFUN-CAPACITORS_100PF-0603-50V-5%"))
    )
    (comp (ref "C43")
      (value "10uF")
      (footprint "eagle-import:SPARKFUN-CAPACITORS_1210")
      (libsource (lib "eagle-import") (part "SPARKFUN-CAPACITORS_10UF-1210-50V-20%"))
    )
    (comp (ref "C45")
      (value "100pF")
      (footprint "eagle-import:SPARKFUN-CAPACITORS_0603")
      (libsource (lib "eagle-import") (part "SPARKFUN-CAPACITORS_100PF-0603-50V-5%"))
    )
    (comp (ref "C46")
      (value "100pF")
      (footprint "eagle-import:SPARKFUN-CAPACITORS_0603")
      (libsource (lib "eagle-import") (part "SPARKFUN-CAPACITORS_100PF-0603-50V-5%"))
    )
    (comp (ref "C47")
      (value "C-EU225-062X268")
      (footprint "eagle-import:C225-062X268")
      (libsource (lib "eagle-import") (part "C-EU225-062X268"))
    )
    (comp (ref "C48")
      (value "C-EU225-062X268")
      (footprint "eagle-import:C225-062X268")
      (libsource (lib "eagle-import") (part "C-EU225-062X268"))
    )
    (comp (ref "D1")
      (value "BAT54SFILM_BAT54SFILM")
      (footprint "eagle-import:BAT54SFILM_SOT105P242X150-3N")
      (fields
        (field (name "MANUFACTURER_PART_NUMBER") "BAT54SFILM")
        (field (name "RS_PART_NUMBER") "7146863P")
      )
      (libsource (lib "eagle-import") (part "BAT54SFILM_BAT54SFILM"))
    )
    (comp (ref "D2")
      (value "STTH112A_STTH112A")
      (footprint "eagle-import:STTH112A_DIOM5126X265N")
      (fields (field (name "MANUFACTURER_PART_NUMBER") "STTH112A") (field (name "RS_PART_NUMBER") "0249319"))
      (libsource (lib "eagle-import") (part "STTH112A_STTH112A"))
    )
    (comp (ref "D3")
      (value "STPS2H100A_STPS2H100A")
      (footprint "eagle-import:STPS2H100A_DIOM5126X265N")
      (fields
        (field (name "MANUFACTURER_PART_NUMBER") "STPS2H100A")
        (field (name "RS_PART_NUMBER") "0249612P")
      )
      (libsource (lib "eagle-import") (part "STPS2H100A_STPS2H100A"))
    )
    (comp (ref "D4")
      (value "BAT20JFILM_BAT20JFILM")
      (footprint "eagle-import:BAT20JFILM_SOD2512X113N")
      (fields
        (field (name "MANUFACTURER_PART_NUMBER") "BAT20JFILM")
        (field (name "RS_PART_NUMBER") "1657545")
      )
      (libsource (lib "eagle-import") (part "BAT20JFILM_BAT20JFILM"))
    )
    (comp (ref "D5")
      (value "STTH112A_STTH112A")
      (footprint "eagle-import:STTH112A_DIOM5126X265N")
      (fields (field (name "MANUFACTURER_PART_NUMBER") "STTH112A") (field (name "RS_PART_NUMBER") "0249319"))
      (libsource (lib "eagle-import") (part "STTH112A_STTH112A"))
    )
    (comp (ref "D6")
      (value "BAT20JFILM_BAT20JFILM")
      (footprint "eagle-import:BAT20JFILM_SOD2512X113N")
      (fields
        (field (name "MANUFACTURER_PART_NUMBER") "BAT20JFILM")
        (field (name "RS_PART_NUMBER") "1657545")
      )
      (libsource (lib "eagle-import") (part "BAT20JFILM_BAT20JFILM"))
    )
    (comp (ref "D7")
      (value "BAT54SFILM_BAT54SFILM")
      (footprint "eagle-import:BAT54SFILM_SOT105P242X150-3N")
      (fields
        (field (name "MANUFACTURER_PART_NUMBER") "BAT54SFILM")
        (field (name "RS_PART_NUMBER") "7146863P")
        (field (name "SPICEPREFIX") "J")
      )
      (libsource (lib "eagle-import") (part "BAT54SFILM_BAT54SFILM"))
    )
    (comp (ref "D8")
      (value "STPS2H100A_STPS2H100A")
      (footprint "eagle-import:STPS2H100A_DIOM5126X265N")
      (fields
        (field (name "MANUFACTURER_PART_NUMBER") "STPS2H100A")
        (field (name "RS_PART_NUMBER") "0249612P")
        (field (name "SPICEPREFIX") "D")
      )
      (libsource (lib "eagle-import") (part "STPS2H100A_STPS2H100A"))
    )
    (comp (ref "D9-D.N.M")
      (value "STPS2H100A_STPS2H100A")
      (footprint "eagle-import:STPS2H100A_DIOM5126X265N")
      (fields
        (field (name "MANUFACTURER_PART_NUMBER") "STPS2H100A")
        (field (name "RS_PART_NUMBER") "0249612P")
      )
      (libsource (lib "eagle-import") (part "STPS2H100A_STPS2H100A"))
    )
    (comp (ref "D9-D.N.M.2")
      (value "STPS2H100A_STPS2H100A")
      (footprint "eagle-import:STPS2H100A_DIOM5126X265N")
      (fields
        (field (name "MANUFACTURER_PART_NUMBER") "STPS2H100A")
        (field (name "RS_PART_NUMBER") "0249612P")
        (field (name "SPICEPREFIX") "D")
      )
      (libsource (lib "eagle-import") (part "STPS2H100A_STPS2H100A"))
    )
    (comp (ref "DL1")
      (value "RED")
      (footprint "eagle-import:SPARKFUN-LED_LED-1206")
      (libsource (lib "eagle-import") (part "SPARKFUN-LED_LED-RED1206"))
    )
    (comp (ref "DL2")
      (value "RED")
      (footprint "eagle-import:SPARKFUN-LED_LED-1206")
      (libsource (lib "eagle-import") (part "SPARKFUN-LED_LED-RED1206"))
    )
    (comp (ref "DL3")
      (value "RED")
      (footprint "eagle-import:SPARKFUN-LED_LED-1206")
      (libsource (lib "eagle-import") (part "SPARKFUN-LED_LED-RED1206"))
    )
    (comp (ref "DL4")
      (value "RED")
      (footprint "eagle-import:SPARKFUN-LED_LED-1206")
      (libsource (lib "eagle-import") (part "SPARKFUN-LED_LED-RED1206"))
    )
    (comp (ref "IC1")
      (value "NATIONAL-SEMICONDUCTOR_LM2936MP-3.0")
      (footprint "eagle-import:NATIONAL-SEMICONDUCTOR_SOT223")
      (fields (field (name "MF") "NATIONAL SEMICONDUCTOR") (field (name "MPN") "LM2936MP-3.0/NOPB"))
      (libsource (lib "eagle-import") (part "NATIONAL-SEMICONDUCTOR_LM2936MP?-3.0"))
    )
    (comp (ref "J1")
      (value "SPARKFUN-CONNECTORS_CONN_12LONGPADS")
      (footprint "eagle-import:SPARKFUN-CONNECTORS_1X12_LONGPADS")
      (libsource (lib "eagle-import") (part "SPARKFUN-CONNECTORS_CONN_12LONGPADS"))
    )
    (comp (ref "J2")
      (value "SPARKFUN-CONNECTORS_CONN_03LONGPADS")
      (footprint "eagle-import:SPARKFUN-CONNECTORS_1X03_LONGPADS")
      (libsource (lib "eagle-import") (part "SPARKFUN-CONNECTORS_CONN_03LONGPADS"))
    )
    (comp (ref "J3")
      (value "SPARKFUN-CONNECTORS_CONN_04LONGPADS")
      (footprint "eagle-import:SPARKFUN-CONNECTORS_1X04_LONGPADS")
      (libsource (lib "eagle-import") (part "SPARKFUN-CONNECTORS_CONN_04LONGPADS"))
    )
    (comp (ref "J4")
      (value "SPARKFUN-CONNECTORS_CONN_04LONGPADS")
      (footprint "eagle-import:SPARKFUN-CONNECTORS_1X04_LONGPADS")
      (libsource (lib "eagle-import") (part "SPARKFUN-CONNECTORS_CONN_04LONGPADS"))
    )
    (comp (ref "MICROCONTROLLER_POWER1")
      (value "SPARKFUN-CONNECTORS_CONN_025MM")
      (footprint "eagle-import:SPARKFUN-CONNECTORS_SCREWTERMINAL-5MM-2")
      (libsource (lib "eagle-import") (part "SPARKFUN-CONNECTORS_CONN_025MM"))
    )
    (comp (ref "Q1")
      (value "C2M0280120D_C2M0280120D")
      (footprint "eagle-import:C2M0280120D_TO544P521X1594X2550-3P")
      (fields
        (field (name "MANUFACTURER_PART_NUMBER") "C2M0280120D")
        (field (name "RS_PART_NUMBER") "9158820P")
      )
      (libsource (lib "eagle-import") (part "C2M0280120D_C2M0280120D"))
    )
    (comp (ref "Q2")
      (value "C2M0280120D_C2M0280120D")
      (footprint "eagle-import:C2M0280120D_TO544P521X1594X2550-3P")
      (fields
        (field (name "MANUFACTURER_PART_NUMBER") "C2M0280120D")
        (field (name "RS_PART_NUMBER") "9158820P")
      )
      (libsource (lib "eagle-import") (part "C2M0280120D_C2M0280120D"))
    )
    (comp (ref "R1")
      (value "1k")
      (footprint "eagle-import:SPARKFUN-RESISTORS_0603")
      (libsource (lib "eagle-import") (part "SPARKFUN-RESISTORS_1KOHM-0603-1/10W-1%"))
    )
    (comp (ref "R1-D.N.M.2")
      (value "0")
      (footprint "eagle-import:SPARKFUN-RESISTORS_0603")
      (libsource (lib "eagle-import") (part "SPARKFUN-RESISTORS_0OHM-0603-1/10W-5%"))
    )
    (comp (ref "R2")
      (value "SPARKFUN-RESISTORS_RESISTOR0805")
      (footprint "eagle-import:SPARKFUN-RESISTORS_0805")
      (libsource (lib "eagle-import") (part "SPARKFUN-RESISTORS_RESISTOR0805"))
    )
    (comp (ref "R3")
      (value "SPARKFUN-RESISTORS_RESISTOR1206")
      (footprint "eagle-import:SPARKFUN-RESISTORS_1206")
      (libsource (lib "eagle-import") (part "SPARKFUN-RESISTORS_RESISTOR1206"))
    )
    (comp (ref "R4")
      (value "SPARKFUN-RESISTORS_RESISTOR1206")
      (footprint "eagle-import:SPARKFUN-RESISTORS_1206")
      (libsource (lib "eagle-import") (part "SPARKFUN-RESISTORS_RESISTOR1206"))
    )
    (comp (ref "R5")
      (value "SPARKFUN-RESISTORS_RESISTOR1206")
      (footprint "eagle-import:SPARKFUN-RESISTORS_1206")
      (libsource (lib "eagle-import") (part "SPARKFUN-RESISTORS_RESISTOR1206"))
    )
    (comp (ref "R6")
      (value "SPARKFUN-RESISTORS_RESISTOR1206")
      (footprint "eagle-import:SPARKFUN-RESISTORS_1206")
      (libsource (lib "eagle-import") (part "SPARKFUN-RESISTORS_RESISTOR1206"))
    )
    (comp (ref "R7")
      (value "47k")
      (footprint "eagle-import:SPARKFUN-RESISTORS_0603")
      (libsource (lib "eagle-import") (part "SPARKFUN-RESISTORS_47KOHM-0603-1/10W-1%"))
    )
    (comp (ref "R8")
      (value "1k")
      (footprint "eagle-import:SPARKFUN-RESISTORS_0603")
      (libsource (lib "eagle-import") (part "SPARKFUN-RESISTORS_1KOHM-0603-1/10W-1%"))
    )
    (comp (ref "R9")
      (value "0")
      (footprint "eagle-import:SPARKFUN-RESISTORS_0603")
      (libsource (lib "eagle-import") (part "SPARKFUN-RESISTORS_0OHM-0603-1/10W-5%"))
    )
    (comp (ref "R10")
      (value "1k")
      (footprint "eagle-import:SPARKFUN-RESISTORS_0603")
      (libsource (lib "eagle-import") (part "SPARKFUN-RESISTORS_1KOHM-0603-1/10W-1%"))
    )
    (comp (ref "R11")
      (value "SPARKFUN-RESISTORS_RESISTOR0603")
      (footprint "eagle-import:SPARKFUN-RESISTORS_0603")
      (libsource (lib "eagle-import") (part "SPARKFUN-RESISTORS_RESISTOR0603"))
    )
    (comp (ref "R12")
      (value "100")
      (footprint "eagle-import:SPARKFUN-RESISTORS_0603")
      (libsource (lib "eagle-import") (part "SPARKFUN-RESISTORS_100OHM-0603-1/4W-5%"))
    )
    (comp (ref "R13")
      (value "100")
      (footprint "eagle-import:SPARKFUN-RESISTORS_0603")
      (libsource (lib "eagle-import") (part "SPARKFUN-RESISTORS_100OHM-0603-1/4W-5%"))
    )
    (comp (ref "R14")
      (value "SPARKFUN-RESISTORS_RESISTOR0603")
      (footprint "eagle-import:SPARKFUN-RESISTORS_0603")
      (libsource (lib "eagle-import") (part "SPARKFUN-RESISTORS_RESISTOR0603"))
    )
    (comp (ref "R15-D.N.M")
      (value "0")
      (footprint "eagle-import:SPARKFUN-RESISTORS_0603")
      (libsource (lib "eagle-import") (part "SPARKFUN-RESISTORS_0OHM-0603-1/10W-5%"))
    )
    (comp (ref "R16")
      (value "100")
      (footprint "eagle-import:SPARKFUN-RESISTORS_0603")
      (libsource (lib "eagle-import") (part "SPARKFUN-RESISTORS_100OHM-0603-1/4W-5%"))
    )
    (comp (ref "R20")
      (value "SPARKFUN-RESISTORS_RESISTOR1206")
      (footprint "eagle-import:SPARKFUN-RESISTORS_1206")
      (libsource (lib "eagle-import") (part "SPARKFUN-RESISTORS_RESISTOR1206"))
    )
    (comp (ref "R21")
      (value "SPARKFUN-RESISTORS_RESISTOR1206")
      (footprint "eagle-import:SPARKFUN-RESISTORS_1206")
      (libsource (lib "eagle-import") (part "SPARKFUN-RESISTORS_RESISTOR1206"))
    )
    (comp (ref "R22")
      (value "1k")
      (footprint "eagle-import:SPARKFUN-RESISTORS_0603")
      (libsource (lib "eagle-import") (part "SPARKFUN-RESISTORS_1KOHM-0603-1/10W-1%"))
    )
    (comp (ref "R23")
      (value "47k")
      (footprint "eagle-import:SPARKFUN-RESISTORS_0603")
      (libsource (lib "eagle-import") (part "SPARKFUN-RESISTORS_47KOHM-0603-1/10W-1%"))
    )
    (comp (ref "R30")
      (value "100")
      (footprint "eagle-import:SPARKFUN-RESISTORS_0603")
      (libsource (lib "eagle-import") (part "SPARKFUN-RESISTORS_100OHM-0603-1/4W-5%"))
    )
    (comp (ref "R31")
      (value "SPARKFUN-RESISTORS_RESISTOR0603")
      (footprint "eagle-import:SPARKFUN-RESISTORS_0603")
      (libsource (lib "eagle-import") (part "SPARKFUN-RESISTORS_RESISTOR0603"))
    )
    (comp (ref "R32")
      (value "SPARKFUN-RESISTORS_RESISTOR0603")
      (footprint "eagle-import:SPARKFUN-RESISTORS_0603")
      (libsource (lib "eagle-import") (part "SPARKFUN-RESISTORS_RESISTOR0603"))
    )
    (comp (ref "R33")
      (value "100")
      (footprint "eagle-import:SPARKFUN-RESISTORS_0603")
      (libsource (lib "eagle-import") (part "SPARKFUN-RESISTORS_100OHM-0603-1/4W-5%"))
    )
    (comp (ref "R34")
      (value "0")
      (footprint "eagle-import:SPARKFUN-RESISTORS_0603")
      (libsource (lib "eagle-import") (part "SPARKFUN-RESISTORS_0OHM-0603-1/10W-5%"))
    )
    (comp (ref "R35")
      (value "SPARKFUN-RESISTORS_RESISTOR0805")
      (footprint "eagle-import:SPARKFUN-RESISTORS_0805")
      (libsource (lib "eagle-import") (part "SPARKFUN-RESISTORS_RESISTOR0805"))
    )
    (comp (ref "R36")
      (value "SPARKFUN-RESISTORS_RESISTOR1206")
      (footprint "eagle-import:SPARKFUN-RESISTORS_1206")
      (libsource (lib "eagle-import") (part "SPARKFUN-RESISTORS_RESISTOR1206"))
    )
    (comp (ref "R37")
      (value "SPARKFUN-RESISTORS_RESISTOR1206")
      (footprint "eagle-import:SPARKFUN-RESISTORS_1206")
      (libsource (lib "eagle-import") (part "SPARKFUN-RESISTORS_RESISTOR1206"))
    )
    (comp (ref "R38")
      (value "SPARKFUN-RESISTORS_RESISTOR1206")
      (footprint "eagle-import:SPARKFUN-RESISTORS_1206")
      (libsource (lib "eagle-import") (part "SPARKFUN-RESISTORS_RESISTOR1206"))
    )
    (comp (ref "R39")
      (value "SPARKFUN-RESISTORS_RESISTOR1206")
      (footprint "eagle-import:SPARKFUN-RESISTORS_1206")
      (libsource (lib "eagle-import") (part "SPARKFUN-RESISTORS_RESISTOR1206"))
    )
    (comp (ref "SICDIODE")
      (value "C2M0280120D_C2M0280120D")
      (footprint "eagle-import:C2M0280120D_TO544P521X1594X2550-3P")
      (fields
        (field (name "MANUFACTURER_PART_NUMBER") "C2M0280120D")
        (field (name "RS_PART_NUMBER") "9158820P")
      )
      (libsource (lib "eagle-import") (part "C2M0280120D_C2M0280120D"))
    )
    (comp (ref "SICDIODE2")
      (value "C2M0280120D_C2M0280120D")
      (footprint "eagle-import:C2M0280120D_TO544P521X1594X2550-3P")
      (fields
        (field (name "MANUFACTURER_PART_NUMBER") "C2M0280120D")
        (field (name "RS_PART_NUMBER") "9158820P")
      )
      (libsource (lib "eagle-import") (part "C2M0280120D_C2M0280120D"))
    )
    (comp (ref "SJ1")
      (value "JUMPER_SJ")
      (footprint "eagle-import:JUMPER_SJ")
      (libsource (lib "eagle-import") (part "JUMPER_SJ"))
    )
    (comp (ref "SJ2")
      (value "JUMPER_SJ")
      (footprint "eagle-import:JUMPER_SJ")
      (libsource (lib "eagle-import") (part "JUMPER_SJ"))
    )
    (comp (ref "SJ3")
      (value "JUMPER_SJ")
      (footprint "eagle-import:JUMPER_SJ")
      (libsource (lib "eagle-import") (part "JUMPER_SJ"))
    )
    (comp (ref "SJ5")
      (value "JUMPER_SJ")
      (footprint "eagle-import:JUMPER_SJ")
      (libsource (lib "eagle-import") (part "JUMPER_SJ"))
    )
    (comp (ref "SJ6")
      (value "JUMPER_SJ")
      (footprint "eagle-import:JUMPER_SJ")
      (libsource (lib "eagle-import") (part "JUMPER_SJ"))
    )
    (comp (ref "SJ7")
      (value "JUMPER_SJ")
      (footprint "eagle-import:JUMPER_SJ")
      (libsource (lib "eagle-import") (part "JUMPER_SJ"))
    )
    (comp (ref "TP1")
      (value "TPTP15SQ")
      (footprint "eagle-import:TP15SQ")
      (libsource (lib "eagle-import") (part "TPTP15SQ"))
    )
    (comp (ref "TP2")
      (value "TPTP15SQ")
      (footprint "eagle-import:TP15SQ")
      (libsource (lib "eagle-import") (part "TPTP15SQ"))
    )
    (comp (ref "TP4")
      (value "TPTP15SQ")
      (footprint "eagle-import:TP15SQ")
      (libsource (lib "eagle-import") (part "TPTP15SQ"))
    )
    (comp (ref "TP5")
      (value "TPTP15SQ")
      (footprint "eagle-import:TP15SQ")
      (libsource (lib "eagle-import") (part "TPTP15SQ"))
    )
    (comp (ref "TP6")
      (value "TPTP15SQ")
      (footprint "eagle-import:TP15SQ")
      (libsource (lib "eagle-import") (part "TPTP15SQ"))
    )
    (comp (ref "U$2")
      (value "SO24E-IC_STGAP1AS")
      (footprint "eagle-import:SO24E-IC_SO24W")
      (libsource (lib "eagle-import") (part "SO24E-IC_STGAP1AS"))
    )
    (comp (ref "U$5")
      (value "SO24E-IC_STGAP1AS")
      (footprint "eagle-import:SO24E-IC_SO24W")
      (libsource (lib "eagle-import") (part "SO24E-IC_STGAP1AS"))
    )
    (comp (ref "U2")
      (value "SAMACSYS_LIB_MGJ2D052005SC")
      (footprint "eagle-import:SAMACSYS_LIB_MGJ2D_7-PIN-SIP")
      (fields (field (name "ARROW_PART_NUMBER") "MGJ2D052005SC") (field (name "RS_PART_NUMBER") "8163506P"))
      (libsource (lib "eagle-import") (part "SAMACSYS_LIB_MGJ2D052005SC"))
    )
    (comp (ref "U3")
      (value "SAMACSYS_LIB_MGJ2D052005SC")
      (footprint "eagle-import:SAMACSYS_LIB_MGJ2D_7-PIN-SIP")
      (fields (field (name "ARROW_PART_NUMBER") "MGJ2D052005SC") (field (name "RS_PART_NUMBER") "8163506P"))
      (libsource (lib "eagle-import") (part "SAMACSYS_LIB_MGJ2D052005SC"))
    )
    (comp (ref "X1")
      (value "234-502")
      (footprint "eagle-import:234-502")
      (libsource (lib "eagle-import") (part "234-502"))
    )
    (comp (ref "X2")
      (value "234-502")
      (footprint "eagle-import:234-502")
      (libsource (lib "eagle-import") (part "234-502"))
    )
    (comp (ref "X3")
      (value "234-502")
      (footprint "eagle-import:234-502")
      (libsource (lib "eagle-import") (part "234-502"))
    )
  )
  (nets
    (net (code "1") (name "CK") (class "Default")
      (node (ref "C22") (pin "1") (pinfunction "1_1") (pintype "passive"))
      (node (ref "C38") (pin "1") (pinfunction "1_1") (pintype "passive"))
      (node (ref "J2") (pin "3") (pinfunction "3_3") (pintype "passive"))
      (node (ref "J3") (pin "3") (pinfunction "3_3") (pintype "passive"))
      (node (ref "J4") (pin "3") (pinfunction "3_3") (pintype "passive"))
      (node (ref "U$2") (pin "5") (pinfunction "CK_5") (pintype "input"))
      (node (ref "U$5") (pin "5") (pinfunction "CK_5") (pintype "input"))
    )
    (net (code "2") (name "CK_2") (class "Default")
      (node (ref "C63") (pin "1") (pinfunction "1_1") (pintype "passive"))
      (node (ref "C85") (pin "1") (pinfunction "1_1") (pintype "passive"))
      (node (ref "J6") (pin "3") (pinfunction "3_3") (pintype "passive"))
      (node (ref "J7") (pin "3") (pinfunction "3_3") (pintype "passive"))
      (node (ref "J8") (pin "3") (pinfunction "3_3") (pintype "passive"))
      (node (ref "U$1") (pin "5") (pinfunction "CK_5") (pintype "input"))
      (node (ref "U$3") (pin "5") (pinfunction "CK_5") (pintype "input"))
    )
    (net (code "3") (name "CS") (class "Default")
      (node (ref "C21") (pin "1") (pinfunction "1_1") (pintype "passive"))
      (node (ref "C37") (pin "1") (pinfunction "1_1") (pintype "passive"))
      (node (ref "J1") (pin "1") (pinfunction "1_1") (pintype "passive"))
      (node (ref "J3") (pin "2") (pinfunction "2_2") (pintype "passive"))
      (node (ref "J4") (pin "2") (pinfunction "2_2") (pintype "passive"))
      (node (ref "U$2") (pin "4") (pinfunction "/CS_4") (pintype "input"))
      (node (ref "U$5") (pin "4") (pinfunction "/CS_4") (pintype "input"))
    )
    (net (code "4") (name "CS_2") (class "Default")
      (node (ref "C62") (pin "1") (pinfunction "1_1") (pintype "passive"))
      (node (ref "C84") (pin "1") (pinfunction "1_1") (pintype "passive"))
      (node (ref "J5") (pin "1") (pinfunction "1_1") (pintype "passive"))
      (node (ref "J7") (pin "2") (pinfunction "2_2") (pintype "passive"))
      (node (ref "J8") (pin "2") (pinfunction "2_2") (pintype "passive"))
      (node (ref "U$1") (pin "4") (pinfunction "/CS_4") (pintype "input"))
      (node (ref "U$3") (pin "4") (pinfunction "/CS_4") (pintype "input"))
    )
    (net (code "5") (name "DESAT") (class "Default")
      (node (ref "C8") (pin "1") (pinfunction "1_1") (pintype "passive"))
      (node (ref "R10") (pin "1") (pinfunction "1_1") (pintype "passive"))
      (node (ref "U$5") (pin "18") (pinfunction "DESAT_18") (pintype "power_in"))
    )
    (net (code "6") (name "DESAT2") (class "Default")
      (node (ref "C20") (pin "1") (pinfunction "1_1") (pintype "passive"))
      (node (ref "R22") (pin "1") (pinfunction "1_1") (pintype "passive"))
      (node (ref "U$2") (pin "18") (pinfunction "DESAT_18") (pintype "power_in"))
    )
    (net (code "7") (name "DESAT2_2") (class "Default")
      (node (ref "C70") (pin "1") (pinfunction "1_1") (pintype "passive"))
      (node (ref "R45") (pin "1") (pinfunction "1_1") (pintype "passive"))
      (node (ref "U$1") (pin "18") (pinfunction "DESAT_18") (pintype "power_in"))
    )
    (net (code "8") (name "DESAT_2") (class "Default")
      (node (ref "C44") (pin "1") (pinfunction "1_1") (pintype "passive"))
      (node (ref "R17") (pin "1") (pinfunction "1_1") (pintype "passive"))
      (node (ref "U$3") (pin "18") (pinfunction "DESAT_18") (pintype "power_in"))
    )
    (net (code "9") (name "GND") (class "Default")
      (node (ref "C13") (pin "2") (pinfunction "2_2") (pintype "passive"))
      (node (ref "C15") (pin "2") (pinfunction "2_2") (pintype "passive"))
      (node (ref "C19") (pin "2") (pinfunction "2_2") (pintype "passive"))
      (node (ref "C21") (pin "2") (pinfunction "2_2") (pintype "passive"))
      (node (ref "C22") (pin "2") (pinfunction "2_2") (pintype "passive"))
      (node (ref "C23") (pin "2") (pinfunction "2_2") (pintype "passive"))
      (node (ref "C34") (pin "2") (pinfunction "2_2") (pintype "passive"))
      (node (ref "C35") (pin "2") (pinfunction "2_2") (pintype "passive"))
      (node (ref "C36") (pin "2") (pinfunction "2_2") (pintype "passive"))
      (node (ref "C37") (pin "2") (pinfunction "2_2") (pintype "passive"))
      (node (ref "C38") (pin "2") (pinfunction "2_2") (pintype "passive"))
      (node (ref "C39") (pin "2") (pinfunction "2_2") (pintype "passive"))
      (node (ref "C4") (pin "2") (pinfunction "2_2") (pintype "passive"))
      (node (ref "C40") (pin "2") (pinfunction "2_2") (pintype "passive"))
      (node (ref "C41") (pin "2") (pinfunction "2_2") (pintype "passive"))
      (node (ref "C42") (pin "2") (pinfunction "2_2") (pintype "passive"))
      (node (ref "C43") (pin "2") (pinfunction "2_2") (pintype "passive"))
      (node (ref "C5") (pin "2") (pinfunction "2_2") (pintype "passive"))
      (node (ref "C59") (pin "2") (pinfunction "2_2") (pintype "passive"))
      (node (ref "C6") (pin "2") (pinfunction "2_2") (pintype "passive"))
      (node (ref "C60") (pin "2") (pinfunction "2_2") (pintype "passive"))
      (node (ref "C61") (pin "2") (pinfunction "2_2") (pintype "passive"))
      (node (ref "C62") (pin "2") (pinfunction "2_2") (pintype "passive"))
      (node (ref "C63") (pin "2") (pinfunction "2_2") (pintype "passive"))
      (node (ref "C64") (pin "2") (pinfunction "2_2") (pintype "passive"))
      (node (ref "C65") (pin "2") (pinfunction "2_2") (pintype "passive"))
      (node (ref "C66") (pin "2") (pinfunction "2_2") (pintype "passive"))
      (node (ref "C67") (pin "2") (pinfunction "2_2") (pintype "passive"))
      (node (ref "C7") (pin "2") (pinfunction "2_2") (pintype "passive"))
      (node (ref "C81") (pin "2") (pinfunction "2_2") (pintype "passive"))
      (node (ref "C82") (pin "2") (pinfunction "2_2") (pintype "passive"))
      (node (ref "C83") (pin "2") (pinfunction "2_2") (pintype "passive"))
      (node (ref "C84") (pin "2") (pinfunction "2_2") (pintype "passive"))
      (node (ref "C85") (pin "2") (pinfunction "2_2") (pintype "passive"))
      (node (ref "C86") (pin "2") (pinfunction "2_2") (pintype "passive"))
      (node (ref "C87") (pin "2") (pinfunction "2_2") (pintype "passive"))
      (node (ref "C88") (pin "2") (pinfunction "2_2") (pintype "passive"))
      (node (ref "C89") (pin "2") (pinfunction "2_2") (pintype "passive"))
      (node (ref "C9") (pin "2") (pinfunction "2_2") (pintype "passive"))
      (node (ref "IC1") (pin "2") (pinfunction "GND_2") (pintype "passive"))
      (node (ref "IC1") (pin "4") (pinfunction "GND_4") (pintype "passive"))
      (node (ref "J1") (pin "11") (pinfunction "11_11") (pintype "passive"))
      (node (ref "J5") (pin "11") (pinfunction "11_11") (pintype "passive"))
      (node (ref "MICROCONTROLLER_POWER1") (pin "1") (pinfunction "1_1") (pintype "passive"))
      (node (ref "U$1") (pin "1") (pinfunction "GND_SIG_1") (pintype "power_in"))
      (node (ref "U$1") (pin "12") (pinfunction "GND_SIG_12") (pintype "power_in"))
      (node (ref "U$2") (pin "1") (pinfunction "GND_SIG_1") (pintype "power_in"))
      (node (ref "U$2") (pin "12") (pinfunction "GND_SIG_12") (pintype "power_in"))
      (node (ref "U$3") (pin "1") (pinfunction "GND_SIG_1") (pintype "power_in"))
      (node (ref "U$3") (pin "12") (pinfunction "GND_SIG_12") (pintype "power_in"))
      (node (ref "U$5") (pin "1") (pinfunction "GND_SIG_1") (pintype "power_in"))
      (node (ref "U$5") (pin "12") (pinfunction "GND_SIG_12") (pintype "power_in"))
      (node (ref "U1") (pin "2") (pinfunction "-VIN_2") (pintype "bidirectional"))
      (node (ref "U2") (pin "2") (pinfunction "-VIN_2") (pintype "bidirectional"))
      (node (ref "U3") (pin "2") (pinfunction "-VIN_2") (pintype "bidirectional"))
      (node (ref "U4") (pin "2") (pinfunction "-VIN_2") (pintype "bidirectional"))
    )
    (net (code "10") (name "GND_SIG") (class "Default")
      (node (ref "C1") (pin "2") (pinfunction "2_2") (pintype "passive"))
      (node (ref "C10") (pin "2") (pinfunction "2_2") (pintype "passive"))
      (node (ref "C11") (pin "2") (pinfunction "2_2") (pintype "passive"))
      (node (ref "C12") (pin "2") (pinfunction "2_2") (pintype "passive"))
      (node (ref "C14") (pin "2") (pinfunction "2_2") (pintype "passive"))
      (node (ref "C16") (pin "2") (pinfunction "2_2") (pintype "passive"))
      (node (ref "C17") (pin "2") (pinfunction "2_2") (pintype "passive"))
      (node (ref "C18") (pin "2") (pinfunction "2_2") (pintype "passive"))
      (node (ref "C2") (pin "2") (pinfunction "2_2") (pintype "passive"))
      (node (ref "C3") (pin "2") (pinfunction "2_2") (pintype "passive"))
      (node (ref "C45") (pin "2") (pinfunction "2_2") (pintype "passive"))
      (node (ref "C8") (pin "2") (pinfunction "2_2") (pintype "passive"))
      (node (ref "D2") (pin "1") (pinfunction "K_1") (pintype "bidirectional"))
      (node (ref "D9-D.N.M.2") (pin "1") (pinfunction "K_1") (pintype "bidirectional"))
      (node (ref "Q1") (pin "3") (pinfunction "S_3") (pintype "power_in"))
      (node (ref "Q2") (pin "2") (pinfunction "D_2") (pintype "power_in"))
      (node (ref "R1") (pin "2") (pinfunction "2_2") (pintype "passive"))
      (node (ref "R21") (pin "2") (pinfunction "2_2") (pintype "passive"))
      (node (ref "SICDIODE") (pin "1") (pinfunction "G_1") (pintype "input"))
      (node (ref "SICDIODE") (pin "3") (pinfunction "S_3") (pintype "power_in"))
      (node (ref "SICDIODE2") (pin "2") (pinfunction "D_2") (pintype "power_in"))
      (node (ref "U$5") (pin "13") (pinfunction "GNDISO_13") (pintype "power_in"))
      (node (ref "U2") (pin "6") (pinfunction "0V_6") (pintype "bidirectional"))
      (node (ref "X2") (pin "A1") (pinfunction "-1_A1") (pintype "passive"))
      (node (ref "X2") (pin "A2") (pinfunction "-2_A2") (pintype "passive"))
    )
    (net (code "11") (name "GND_SIG2") (class "Default")
      (node (ref "C20") (pin "2") (pinfunction "2_2") (pintype "passive"))
      (node (ref "C24") (pin "2") (pinfunction "2_2") (pintype "passive"))
      (node (ref "C25") (pin "2") (pinfunction "2_2") (pintype "passive"))
      (node (ref "C26") (pin "2") (pinfunction "2_2") (pintype "passive"))
      (node (ref "C27") (pin "2") (pinfunction "2_2") (pintype "passive"))
      (node (ref "C28") (pin "2") (pinfunction "2_2") (pintype "passive"))
      (node (ref "C29") (pin "2") (pinfunction "2_2") (pintype "passive"))
      (node (ref "C30") (pin "2") (pinfunction "2_2") (pintype "passive"))
      (node (ref "C31") (pin "2") (pinfunction "2_2") (pintype "passive"))
      (node (ref "C32") (pin "2") (pinfunction "2_2") (pintype "passive"))
      (node (ref "C33") (pin "2") (pinfunction "2_2") (pintype "passive"))
      (node (ref "C46") (pin "2") (pinfunction "2_2") (pintype "passive"))
      (node (ref "C47") (pin "2") (pinfunction "2_2") (pintype "passive"))
      (node (ref "C48") (pin "2") (pinfunction "2_2") (pintype "passive"))
      (node (ref "Q2") (pin "3") (pinfunction "S_3") (pintype "power_in"))
      (node (ref "R8") (pin "2") (pinfunction "2_2") (pintype "passive"))
      (node (ref "SICDIODE2") (pin "1") (pinfunction "G_1") (pintype "input"))
      (node (ref "SICDIODE2") (pin "3") (pinfunction "S_3") (pintype "power_in"))
      (node (ref "U$2") (pin "13") (pinfunction "GNDISO_13") (pintype "power_in"))
      (node (ref "U3") (pin "6") (pinfunction "0V_6") (pintype "bidirectional"))
      (node (ref "X3") (pin "A1") (pinfunction "-1_A1") (pintype "passive"))
      (node (ref "X3") (pin "A2") (pinfunction "-2_A2") (pintype "passive"))
    )
    (net (code "12") (name "GND_SIG2_2") (class "Default")
      (node (ref "C70") (pin "2") (pinfunction "2_2") (pintype "passive"))
      (node (ref "C71") (pin "2") (pinfunction "2_2") (pintype "passive"))
      (node (ref "C72") (pin "2") (pinfunction "2_2") (pintype "passive"))
      (node (ref "C73") (pin "2") (pinfunction "2_2") (pintype "passive"))
      (node (ref "C74") (pin "2") (pinfunction "2_2") (pintype "passive"))
      (node (ref "C75") (pin "2") (pinfunction "2_2") (pintype "passive"))
      (node (ref "C76") (pin "2") (pinfunction "2_2") (pintype "passive"))
      (node (ref "C77") (pin "2") (pinfunction "2_2") (pintype "passive"))
      (node (ref "C78") (pin "2") (pinfunction "2_2") (pintype "passive"))
      (node (ref "C79") (pin "2") (pinfunction "2_2") (pintype "passive"))
      (node (ref "C80") (pin "2") (pinfunction "2_2") (pintype "passive"))
      (node (ref "C92") (pin "2") (pinfunction "2_2") (pintype "passive"))
      (node (ref "C93") (pin "2") (pinfunction "2_2") (pintype "passive"))
      (node (ref "C94") (pin "2") (pinfunction "2_2") (pintype "passive"))
      (node (ref "Q4") (pin "3") (pinfunction "S_3") (pintype "power_in"))
      (node (ref "R44") (pin "2") (pinfunction "2_2") (pintype "passive"))
      (node (ref "SICDIODE3") (pin "1") (pinfunction "G_1") (pintype "input"))
      (node (ref "SICDIODE3") (pin "3") (pinfunction "S_3") (pintype "power_in"))
      (node (ref "U$1") (pin "13") (pinfunction "GNDISO_13") (pintype "power_in"))
      (node (ref "U4") (pin "6") (pinfunction "0V_6") (pintype "bidirectional"))
      (node (ref "X6") (pin "A1") (pinfunction "-1_A1") (pintype "passive"))
      (node (ref "X6") (pin "A2") (pinfunction "-2_A2") (pintype "passive"))
    )
    (net (code "13") (name "GND_SIG_2") (class "Default")
      (node (ref "C44") (pin "2") (pinfunction "2_2") (pintype "passive"))
      (node (ref "C49") (pin "2") (pinfunction "2_2") (pintype "passive"))
      (node (ref "C50") (pin "2") (pinfunction "2_2") (pintype "passive"))
      (node (ref "C51") (pin "2") (pinfunction "2_2") (pintype "passive"))
      (node (ref "C52") (pin "2") (pinfunction "2_2") (pintype "passive"))
      (node (ref "C53") (pin "2") (pinfunction "2_2") (pintype "passive"))
      (node (ref "C54") (pin "2") (pinfunction "2_2") (pintype "passive"))
      (node (ref "C55") (pin "2") (pinfunction "2_2") (pintype "passive"))
      (node (ref "C56") (pin "2") (pinfunction "2_2") (pintype "passive"))
      (node (ref "C57") (pin "2") (pinfunction "2_2") (pintype "passive"))
      (node (ref "C58") (pin "2") (pinfunction "2_2") (pintype "passive"))
      (node (ref "C91") (pin "2") (pinfunction "2_2") (pintype "passive"))
      (node (ref "D13") (pin "1") (pinfunction "K_1") (pintype "bidirectional"))
      (node (ref "D9-D.N.M.1") (pin "1") (pinfunction "K_1") (pintype "bidirectional"))
      (node (ref "Q3") (pin "3") (pinfunction "S_3") (pintype "power_in"))
      (node (ref "Q4") (pin "2") (pinfunction "D_2") (pintype "power_in"))
      (node (ref "R15") (pin "2") (pinfunction "2_2") (pintype "passive"))
      (node (ref "R58") (pin "2") (pinfunction "2_2") (pintype "passive"))
      (node (ref "SICDIODE1") (pin "1") (pinfunction "G_1") (pintype "input"))
      (node (ref "SICDIODE1") (pin "3") (pinfunction "S_3") (pintype "power_in"))
      (node (ref "SICDIODE3") (pin "2") (pinfunction "D_2") (pintype "power_in"))
      (node (ref "U$3") (pin "13") (pinfunction "GNDISO_13") (pintype "power_in"))
      (node (ref "U1") (pin "6") (pinfunction "0V_6") (pintype "bidirectional"))
      (node (ref "X5") (pin "A1") (pinfunction "-1_A1") (pintype "passive"))
      (node (ref "X5") (pin "A2") (pinfunction "-2_A2") (pintype "passive"))
    )
    (net (code "14") (name "GOFF") (class "Default")
      (node (ref "R3") (pin "1") (pinfunction "1_1") (pintype "passive"))
      (node (ref "R4") (pin "1") (pinfunction "1_1") (pintype "passive"))
      (node (ref "U$5") (pin "21") (pinfunction "GOFF_21") (pintype "power_in"))
    )
    (net (code "15") (name "GOFF2") (class "Default")
      (node (ref "R36") (pin "1") (pinfunction "1_1") (pintype "passive"))
      (node (ref "R37") (pin "1") (pinfunction "1_1") (pintype "passive"))
      (node (ref "U$2") (pin "21") (pinfunction "GOFF_21") (pintype "power_in"))
    )
    (net (code "16") (name "GOFF2_2") (class "Default")
      (node (ref "R53") (pin "1") (pinfunction "1_1") (pintype "passive"))
      (node (ref "R54") (pin "1") (pinfunction "1_1") (pintype "passive"))
      (node (ref "U$1") (pin "21") (pinfunction "GOFF_21") (pintype "power_in"))
    )
    (net (code "17") (name "GOFF_2") (class "Default")
      (node (ref "R40") (pin "1") (pinfunction "1_1") (pintype "passive"))
      (node (ref "R41") (pin "1") (pinfunction "1_1") (pintype "passive"))
      (node (ref "U$3") (pin "21") (pinfunction "GOFF_21") (pintype "power_in"))
    )
    (net (code "18") (name "GON") (class "Default")
      (node (ref "R5") (pin "1") (pinfunction "1_1") (pintype "passive"))
      (node (ref "R6") (pin "1") (pinfunction "1_1") (pintype "passive"))
      (node (ref "U$5") (pin "20") (pinfunction "GON_20") (pintype "power_in"))
    )
    (net (code "19") (name "GON2") (class "Default")
      (node (ref "R38") (pin "1") (pinfunction "1_1") (pintype "passive"))
      (node (ref "R39") (pin "1") (pinfunction "1_1") (pintype "passive"))
      (node (ref "U$2") (pin "20") (pinfunction "GON_20") (pintype "power_in"))
    )
    (net (code "20") (name "GON2_2") (class "Default")
      (node (ref "R55") (pin "1") (pinfunction "1_1") (pintype "passive"))
      (node (ref "R56") (pin "1") (pinfunction "1_1") (pintype "passive"))
      (node (ref "U$1") (pin "20") (pinfunction "GON_20") (pintype "power_in"))
    )
    (net (code "21") (name "GON_2") (class "Default")
      (node (ref "R42") (pin "1") (pinfunction "1_1") (pintype "passive"))
      (node (ref "R43") (pin "1") (pinfunction "1_1") (pintype "passive"))
      (node (ref "U$3") (pin "20") (pinfunction "GON_20") (pintype "power_in"))
    )
    (net (code "22") (name "IN+") (class "Default")
      (node (ref "DL3") (pin "C") (pinfunction "C_C") (pintype "passive"))
      (node (ref "J1") (pin "4") (pinfunction "4_4") (pintype "passive"))
      (node (ref "R13") (pin "1") (pinfunction "1_1") (pintype "passive"))
      (node (ref "R33") (pin "1") (pinfunction "1_1") (pintype "passive"))
    )
    (net (code "23") (name "IN+_2") (class "Default")
      (node (ref "DL7") (pin "C") (pinfunction "C_C") (pintype "passive"))
      (node (ref "J5") (pin "4") (pinfunction "4_4") (pintype "passive"))
      (node (ref "R24") (pin "1") (pinfunction "1_1") (pintype "passive"))
      (node (ref "R50") (pin "1") (pinfunction "1_1") (pintype "passive"))
    )
    (net (code "24") (name "IN+_PIN") (class "Default")
      (node (ref "C13") (pin "1") (pinfunction "1_1") (pintype "passive"))
      (node (ref "R13") (pin "2") (pinfunction "2_2") (pintype "passive"))
      (node (ref "U$5") (pin "9") (pinfunction "IN+_9") (pintype "input"))
    )
    (net (code "25") (name "IN+_PIN2") (class "Default")
      (node (ref "C40") (pin "1") (pinfunction "1_1") (pintype "passive"))
      (node (ref "R30") (pin "2") (pinfunction "2_2") (pintype "passive"))
      (node (ref "U$2") (pin "9") (pinfunction "IN+_9") (pintype "input"))
    )
    (net (code "26") (name "IN+_PIN2_2") (class "Default")
      (node (ref "C87") (pin "1") (pinfunction "1_1") (pintype "passive"))
      (node (ref "R47") (pin "2") (pinfunction "2_2") (pintype "passive"))
      (node (ref "U$1") (pin "9") (pinfunction "IN+_9") (pintype "input"))
    )
    (net (code "27") (name "IN+_PIN_2") (class "Default")
      (node (ref "C65") (pin "1") (pinfunction "1_1") (pintype "passive"))
      (node (ref "R24") (pin "2") (pinfunction "2_2") (pintype "passive"))
      (node (ref "U$3") (pin "9") (pinfunction "IN+_9") (pintype "input"))
    )
    (net (code "28") (name "IN-{slash}DIAG2") (class "Default")
      (node (ref "DL1") (pin "C") (pinfunction "C_C") (pintype "passive"))
      (node (ref "J1") (pin "5") (pinfunction "5_5") (pintype "passive"))
      (node (ref "R12") (pin "1") (pinfunction "1_1") (pintype "passive"))
      (node (ref "R30") (pin "1") (pinfunction "1_1") (pintype "passive"))
    )
    (net (code "29") (name "IN-{slash}DIAG2_2") (class "Default")
      (node (ref "DL5") (pin "C") (pinfunction "C_C") (pintype "passive"))
      (node (ref "J5") (pin "5") (pinfunction "5_5") (pintype "passive"))
      (node (ref "R27") (pin "1") (pinfunction "1_1") (pintype "passive"))
      (node (ref "R47") (pin "1") (pinfunction "1_1") (pintype "passive"))
    )
    (net (code "30") (name "IN-{slash}DIAG2_PIN") (class "Default")
      (node (ref "C9") (pin "1") (pinfunction "1_1") (pintype "passive"))
      (node (ref "R12") (pin "2") (pinfunction "2_2") (pintype "passive"))
      (node (ref "U$5") (pin "8") (pinfunction "IN-/DIAG2_8") (pintype "bidirectional"))
    )
    (net (code "31") (name "IN-{slash}DIAG2_PIN2") (class "Default")
      (node (ref "C42") (pin "1") (pinfunction "1_1") (pintype "passive"))
      (node (ref "R33") (pin "2") (pinfunction "2_2") (pintype "passive"))
      (node (ref "U$2") (pin "8") (pinfunction "IN-/DIAG2_8") (pintype "bidirectional"))
    )
    (net (code "32") (name "IN-{slash}DIAG2_PIN2_2") (class "Default")
      (node (ref "C89") (pin "1") (pinfunction "1_1") (pintype "passive"))
      (node (ref "R50") (pin "2") (pinfunction "2_2") (pintype "passive"))
      (node (ref "U$1") (pin "8") (pinfunction "IN-/DIAG2_8") (pintype "bidirectional"))
    )
    (net (code "33") (name "IN-{slash}DIAG2_PIN_2") (class "Default")
      (node (ref "C67") (pin "1") (pinfunction "1_1") (pintype "passive"))
      (node (ref "R27") (pin "2") (pinfunction "2_2") (pintype "passive"))
      (node (ref "U$3") (pin "8") (pinfunction "IN-/DIAG2_8") (pintype "bidirectional"))
    )
    (net (code "34") (name "N$8") (class "Default")
      (node (ref "D1") (pin "3") (pinfunction "COM_3") (pintype "bidirectional"))
      (node (ref "Q1") (pin "1") (pinfunction "G_1") (pintype "input"))
      (node (ref "R2") (pin "1") (pinfunction "1_1") (pintype "passive"))
      (node (ref "R3") (pin "2") (pinfunction "2_2") (pintype "passive"))
      (node (ref "R4") (pin "2") (pinfunction "2_2") (pintype "passive"))
      (node (ref "R5") (pin "2") (pinfunction "2_2") (pintype "passive"))
      (node (ref "R6") (pin "2") (pinfunction "2_2") (pintype "passive"))
      (node (ref "R7") (pin "1") (pinfunction "1_1") (pintype "passive"))
      (node (ref "TP2") (pin "TP") (pinfunction "TP_TP") (pintype "input"))
      (node (ref "U$5") (pin "22") (pinfunction "CLAMP_22") (pintype "power_in"))
    )
    (net (code "35") (name "N$8_2") (class "Default")
      (node (ref "D11") (pin "3") (pinfunction "COM_3") (pintype "bidirectional"))
      (node (ref "Q3") (pin "1") (pinfunction "G_1") (pintype "input"))
      (node (ref "R18") (pin "1") (pinfunction "1_1") (pintype "passive"))
      (node (ref "R29") (pin "1") (pinfunction "1_1") (pintype "passive"))
      (node (ref "R40") (pin "2") (pinfunction "2_2") (pintype "passive"))
      (node (ref "R41") (pin "2") (pinfunction "2_2") (pintype "passive"))
      (node (ref "R42") (pin "2") (pinfunction "2_2") (pintype "passive"))
      (node (ref "R43") (pin "2") (pinfunction "2_2") (pintype "passive"))
      (node (ref "TP7") (pin "TP") (pinfunction "TP_TP") (pintype "input"))
      (node (ref "U$3") (pin "22") (pinfunction "CLAMP_22") (pintype "power_in"))
    )
    (net (code "36") (name "N$21") (class "Default")
      (node (ref "C47") (pin "1") (pinfunction "1_1") (pintype "passive"))
      (node (ref "C48") (pin "1") (pinfunction "1_1") (pintype "passive"))
      (node (ref "D5") (pin "1") (pinfunction "K_1") (pintype "bidirectional"))
      (node (ref "D9-D.N.M") (pin "1") (pinfunction "K_1") (pintype "bidirectional"))
      (node (ref "Q1") (pin "2") (pinfunction "D_2") (pintype "power_in"))
      (node (ref "R20") (pin "2") (pinfunction "2_2") (pintype "passive"))
      (node (ref "SICDIODE") (pin "2") (pinfunction "D_2") (pintype "power_in"))
      (node (ref "TP1") (pin "TP") (pinfunction "TP_TP") (pintype "input"))
      (node (ref "X1") (pin "A1") (pinfunction "-1_A1") (pintype "passive"))
      (node (ref "X1") (pin "A2") (pinfunction "-2_A2") (pintype "passive"))
    )
    (net (code "37") (name "N$21_2") (class "Default")
      (node (ref "C93") (pin "1") (pinfunction "1_1") (pintype "passive"))
      (node (ref "C94") (pin "1") (pinfunction "1_1") (pintype "passive"))
      (node (ref "D9") (pin "1") (pinfunction "K_1") (pintype "bidirectional"))
      (node (ref "D9-D.N.M1") (pin "1") (pinfunction "K_1") (pintype "bidirectional"))
      (node (ref "Q3") (pin "2") (pinfunction "D_2") (pintype "power_in"))
      (node (ref "R57") (pin "2") (pinfunction "2_2") (pintype "passive"))
      (node (ref "SICDIODE1") (pin "2") (pinfunction "D_2") (pintype "power_in"))
      (node (ref "TP3") (pin "TP") (pinfunction "TP_TP") (pintype "input"))
      (node (ref "X4") (pin "A1") (pinfunction "-1_A1") (pintype "passive"))
      (node (ref "X4") (pin "A2") (pinfunction "-2_A2") (pintype "passive"))
    )
    (net (code "38") (name "N$82") (class "Default")
      (node (ref "D7") (pin "3") (pinfunction "COM_3") (pintype "bidirectional"))
      (node (ref "Q2") (pin "1") (pinfunction "G_1") (pintype "input"))
      (node (ref "R23") (pin "1") (pinfunction "1_1") (pintype "passive"))
      (node (ref "R35") (pin "1") (pinfunction "1_1") (pintype "passive"))
      (node (ref "R36") (pin "2") (pinfunction "2_2") (pintype "passive"))
      (node (ref "R37") (pin "2") (pinfunction "2_2") (pintype "passive"))
      (node (ref "R38") (pin "2") (pinfunction "2_2") (pintype "passive"))
      (node (ref "R39") (pin "2") (pinfunction "2_2") (pintype "passive"))
      (node (ref "TP4") (pin "TP") (pinfunction "TP_TP") (pintype "input"))
      (node (ref "U$2") (pin "22") (pinfunction "CLAMP_22") (pintype "power_in"))
    )
    (net (code "39") (name "N$82_2") (class "Default")
      (node (ref "D15") (pin "3") (pinfunction "COM_3") (pintype "bidirectional"))
      (node (ref "Q4") (pin "1") (pinfunction "G_1") (pintype "input"))
      (node (ref "R46") (pin "1") (pinfunction "1_1") (pintype "passive"))
      (node (ref "R52") (pin "1") (pinfunction "1_1") (pintype "passive"))
      (node (ref "R53") (pin "2") (pinfunction "2_2") (pintype "passive"))
      (node (ref "R54") (pin "2") (pinfunction "2_2") (pintype "passive"))
      (node (ref "R55") (pin "2") (pinfunction "2_2") (pintype "passive"))
      (node (ref "R56") (pin "2") (pinfunction "2_2") (pintype "passive"))
      (node (ref "TP8") (pin "TP") (pinfunction "TP_TP") (pintype "input"))
      (node (ref "U$1") (pin "22") (pinfunction "CLAMP_22") (pintype "power_in"))
    )
    (net (code "40") (name "NONE") (class "Default")
      (node (ref "J2") (pin "1") (pinfunction "1_1") (pintype "passive"))
    )
    (net (code "41") (name "NONE_2") (class "Default")
      (node (ref "J6") (pin "1") (pinfunction "1_1") (pintype "passive"))
    )
    (net (code "42") (name "Net-(C45-Pad1)") (class "Default")
      (node (ref "C45") (pin "1") (pinfunction "1_1") (pintype "passive"))
      (node (ref "R20") (pin "1") (pinfunction "1_1") (pintype "passive"))
    )
    (net (code "43") (name "Net-(C46-Pad1)") (class "Default")
      (node (ref "C46") (pin "1") (pinfunction "1_1") (pintype "passive"))
      (node (ref "R21") (pin "1") (pinfunction "1_1") (pintype "passive"))
    )
    (net (code "44") (name "Net-(C91-Pad1)") (class "Default")
      (node (ref "C91") (pin "1") (pinfunction "1_1") (pintype "passive"))
      (node (ref "R57") (pin "1") (pinfunction "1_1") (pintype "passive"))
    )
    (net (code "45") (name "Net-(C92-Pad1)") (class "Default")
      (node (ref "C92") (pin "1") (pinfunction "1_1") (pintype "passive"))
      (node (ref "R58") (pin "1") (pinfunction "1_1") (pintype "passive"))
    )
    (net (code "46") (name "Net-(D2-A)") (class "Default")
      (node (ref "D2") (pin "2") (pinfunction "A_2") (pintype "bidirectional"))
      (node (ref "R22") (pin "2") (pinfunction "2_2") (pintype "passive"))
    )
    (net (code "47") (name "Net-(D3-A)") (class "Default")
      (node (ref "D3") (pin "2") (pinfunction "A_2") (pintype "bidirectional"))
      (node (ref "D4") (pin "2") (pinfunction "A_2") (pintype "bidirectional"))
      (node (ref "D9-D.N.M") (pin "2") (pinfunction "A_2") (pintype "bidirectional"))
    )
    (net (code "48") (name "Net-(D3-K)") (class "Default")
      (node (ref "D3") (pin "1") (pinfunction "K_1") (pintype "bidirectional"))
      (node (ref "R2") (pin "2") (pinfunction "2_2") (pintype "passive"))
    )
    (net (code "49") (name "Net-(D4-K)") (class "Default")
      (node (ref "D4") (pin "1") (pinfunction "K_1") (pintype "bidirectional"))
      (node (ref "R15-D.N.M") (pin "1") (pinfunction "1_1") (pintype "passive"))
    )
    (net (code "50") (name "Net-(D5-A)") (class "Default")
      (node (ref "D5") (pin "2") (pinfunction "A_2") (pintype "bidirectional"))
      (node (ref "R10") (pin "2") (pinfunction "2_2") (pintype "passive"))
    )
    (net (code "51") (name "Net-(D6-A)") (class "Default")
      (node (ref "D6") (pin "2") (pinfunction "A_2") (pintype "bidirectional"))
      (node (ref "D8") (pin "2") (pinfunction "A_2") (pintype "bidirectional"))
      (node (ref "D9-D.N.M.2") (pin "2") (pinfunction "A_2") (pintype "bidirectional"))
    )
    (net (code "52") (name "Net-(D6-K)") (class "Default")
      (node (ref "D6") (pin "1") (pinfunction "K_1") (pintype "bidirectional"))
      (node (ref "R1-D.N.M.2") (pin "1") (pinfunction "1_1") (pintype "passive"))
    )
    (net (code "53") (name "Net-(D8-K)") (class "Default")
      (node (ref "D8") (pin "1") (pinfunction "K_1") (pintype "bidirectional"))
      (node (ref "R35") (pin "2") (pinfunction "2_2") (pintype "passive"))
    )
    (net (code "54") (name "Net-(D9-A)") (class "Default")
      (node (ref "D9") (pin "2") (pinfunction "A_2") (pintype "bidirectional"))
      (node (ref "R17") (pin "2") (pinfunction "2_2") (pintype "passive"))
    )
    (net (code "55") (name "Net-(D10-A)") (class "Default")
      (node (ref "D10") (pin "2") (pinfunction "A_2") (pintype "bidirectional"))
      (node (ref "D12") (pin "2") (pinfunction "A_2") (pintype "bidirectional"))
      (node (ref "D9-D.N.M1") (pin "2") (pinfunction "A_2") (pintype "bidirectional"))
    )
    (net (code "56") (name "Net-(D10-K)") (class "Default")
      (node (ref "D10") (pin "1") (pinfunction "K_1") (pintype "bidirectional"))
      (node (ref "R15-D.N.M1") (pin "1") (pinfunction "1_1") (pintype "passive"))
    )
    (net (code "57") (name "Net-(D12-K)") (class "Default")
      (node (ref "D12") (pin "1") (pinfunction "K_1") (pintype "bidirectional"))
      (node (ref "R29") (pin "2") (pinfunction "2_2") (pintype "passive"))
    )
    (net (code "58") (name "Net-(D13-A)") (class "Default")
      (node (ref "D13") (pin "2") (pinfunction "A_2") (pintype "bidirectional"))
      (node (ref "R45") (pin "2") (pinfunction "2_2") (pintype "passive"))
    )
    (net (code "59") (name "Net-(D14-A)") (class "Default")
      (node (ref "D14") (pin "2") (pinfunction "A_2") (pintype "bidirectional"))
      (node (ref "D16") (pin "2") (pinfunction "A_2") (pintype "bidirectional"))
      (node (ref "D9-D.N.M.1") (pin "2") (pinfunction "A_2") (pintype "bidirectional"))
    )
    (net (code "60") (name "Net-(D14-K)") (class "Default")
      (node (ref "D14") (pin "1") (pinfunction "K_1") (pintype "bidirectional"))
      (node (ref "R1-D.N.M.1") (pin "1") (pinfunction "1_1") (pintype "passive"))
    )
    (net (code "61") (name "Net-(D16-K)") (class "Default")
      (node (ref "D16") (pin "1") (pinfunction "K_1") (pintype "bidirectional"))
      (node (ref "R52") (pin "2") (pinfunction "2_2") (pintype "passive"))
    )
    (net (code "62") (name "Net-(DL1-PadA)") (class "Default")
      (node (ref "DL1") (pin "A") (pinfunction "A_A") (pintype "passive"))
      (node (ref "R11") (pin "1") (pinfunction "1_1") (pintype "passive"))
    )
    (net (code "63") (name "Net-(DL2-PadA)") (class "Default")
      (node (ref "DL2") (pin "A") (pinfunction "A_A") (pintype "passive"))
      (node (ref "R14") (pin "1") (pinfunction "1_1") (pintype "passive"))
    )
    (net (code "64") (name "Net-(DL3-PadA)") (class "Default")
      (node (ref "DL3") (pin "A") (pinfunction "A_A") (pintype "passive"))
      (node (ref "R31") (pin "1") (pinfunction "1_1") (pintype "passive"))
    )
    (net (code "65") (name "Net-(DL4-PadA)") (class "Default")
      (node (ref "DL4") (pin "A") (pinfunction "A_A") (pintype "passive"))
      (node (ref "R32") (pin "1") (pinfunction "1_1") (pintype "passive"))
    )
    (net (code "66") (name "Net-(DL5-PadA)") (class "Default")
      (node (ref "DL5") (pin "A") (pinfunction "A_A") (pintype "passive"))
      (node (ref "R25") (pin "1") (pinfunction "1_1") (pintype "passive"))
    )
    (net (code "67") (name "Net-(DL6-PadA)") (class "Default")
      (node (ref "DL6") (pin "A") (pinfunction "A_A") (pintype "passive"))
      (node (ref "R26") (pin "1") (pinfunction "1_1") (pintype "passive"))
    )
    (net (code "68") (name "Net-(DL7-PadA)") (class "Default")
      (node (ref "DL7") (pin "A") (pinfunction "A_A") (pintype "passive"))
      (node (ref "R48") (pin "1") (pinfunction "1_1") (pintype "passive"))
    )
    (net (code "69") (name "Net-(DL8-PadA)") (class "Default")
      (node (ref "DL8") (pin "A") (pinfunction "A_A") (pintype "passive"))
      (node (ref "R49") (pin "1") (pinfunction "1_1") (pintype "passive"))
    )
    (net (code "70") (name "Net-(IC1-VIN)") (class "Default")
      (node (ref "C6") (pin "1") (pinfunction "1_1") (pintype "passive"))
      (node (ref "IC1") (pin "1") (pinfunction "VIN_1") (pintype "input"))
      (node (ref "MICROCONTROLLER_POWER1") (pin "2") (pinfunction "2_2") (pintype "passive"))
    )
    (net (code "71") (name "Net-(U$1-ASC)") (class "Default")
      (node (ref "R44") (pin "1") (pinfunction "1_1") (pintype "passive"))
      (node (ref "U$1") (pin "24") (pinfunction "ASC_24") (pintype "power_in"))
    )
    (net (code "72") (name "Net-(U$2-ASC)") (class "Default")
      (node (ref "R8") (pin "1") (pinfunction "1_1") (pintype "passive"))
      (node (ref "U$2") (pin "24") (pinfunction "ASC_24") (pintype "power_in"))
    )
    (net (code "73") (name "Net-(U$3-ASC)") (class "Default")
      (node (ref "R15") (pin "1") (pinfunction "1_1") (pintype "passive"))
      (node (ref "U$3") (pin "24") (pinfunction "ASC_24") (pintype "power_in"))
    )
    (net (code "74") (name "Net-(U$5-ASC)") (class "Default")
      (node (ref "R1") (pin "1") (pinfunction "1_1") (pintype "passive"))
      (node (ref "U$5") (pin "24") (pinfunction "ASC_24") (pintype "power_in"))
    )
    (net (code "75") (name "SD") (class "Default")
      (node (ref "J1") (pin "2") (pinfunction "2_2") (pintype "passive"))
      (node (ref "R16") (pin "1") (pinfunction "1_1") (pintype "passive"))
    )
    (net (code "76") (name "SDI") (class "Default")
      (node (ref "J1") (pin "9") (pinfunction "9_9") (pintype "passive"))
      (node (ref "SJ2") (pin "2") (pinfunction "2_2") (pintype "passive"))
    )
    (net (code "77") (name "SDI2") (class "Default")
      (node (ref "SJ5") (pin "2") (pinfunction "2_2") (pintype "passive"))
      (node (ref "SJ7") (pin "2") (pinfunction "2_2") (pintype "passive"))
    )
    (net (code "78") (name "SDI2_2") (class "Default")
      (node (ref "SJ11") (pin "2") (pinfunction "2_2") (pintype "passive"))
      (node (ref "SJ8") (pin "2") (pinfunction "2_2") (pintype "passive"))
    )
    (net (code "79") (name "SDI_2") (class "Default")
      (node (ref "J5") (pin "9") (pinfunction "9_9") (pintype "passive"))
      (node (ref "SJ9") (pin "2") (pinfunction "2_2") (pintype "passive"))
    )
    (net (code "80") (name "SDI_PIN") (class "Default")
      (node (ref "C23") (pin "1") (pinfunction "1_1") (pintype "passive"))
      (node (ref "J3") (pin "4") (pinfunction "4_4") (pintype "passive"))
      (node (ref "SJ2") (pin "1") (pinfunction "1_1") (pintype "passive"))
      (node (ref "U$5") (pin "3") (pinfunction "SDI_3") (pintype "input"))
    )
    (net (code "81") (name "SDI_PIN2") (class "Default")
      (node (ref "C39") (pin "1") (pinfunction "1_1") (pintype "passive"))
      (node (ref "SJ7") (pin "1") (pinfunction "1_1") (pintype "passive"))
      (node (ref "U$2") (pin "3") (pinfunction "SDI_3") (pintype "input"))
    )
    (net (code "82") (name "SDI_PIN2_2") (class "Default")
      (node (ref "C86") (pin "1") (pinfunction "1_1") (pintype "passive"))
      (node (ref "SJ11") (pin "1") (pinfunction "1_1") (pintype "passive"))
      (node (ref "U$1") (pin "3") (pinfunction "SDI_3") (pintype "input"))
    )
    (net (code "83") (name "SDO") (class "Default")
      (node (ref "J1") (pin "10") (pinfunction "10_10") (pintype "passive"))
      (node (ref "SJ1") (pin "1") (pinfunction "1_1") (pintype "passive"))
    )
    (net (code "84") (name "SDO_2") (class "Default")
      (node (ref "J5") (pin "10") (pinfunction "10_10") (pintype "passive"))
      (node (ref "SJ12") (pin "1") (pinfunction "1_1") (pintype "passive"))
    )
    (net (code "85") (name "SDO_PIN") (class "Default")
      (node (ref "SJ5") (pin "1") (pinfunction "1_1") (pintype "passive"))
      (node (ref "U$5") (pin "2") (pinfunction "SDO_2") (pintype "bidirectional"))
    )
    (net (code "86") (name "SDO_PIN2") (class "Default")
      (node (ref "C64") (pin "1") (pinfunction "1_1") (pintype "passive"))
      (node (ref "J4") (pin "4") (pinfunction "4_4") (pintype "passive"))
      (node (ref "J7") (pin "4") (pinfunction "4_4") (pintype "passive"))
      (node (ref "SJ1") (pin "2") (pinfunction "2_2") (pintype "passive"))
      (node (ref "SJ9") (pin "1") (pinfunction "1_1") (pintype "passive"))
      (node (ref "U$2") (pin "2") (pinfunction "SDO_2") (pintype "bidirectional"))
      (node (ref "U$3") (pin "3") (pinfunction "SDI_3") (pintype "input"))
    )
    (net (code "87") (name "SDO_PIN2_2") (class "Default")
      (node (ref "J8") (pin "4") (pinfunction "4_4") (pintype "passive"))
      (node (ref "SJ12") (pin "2") (pinfunction "2_2") (pintype "passive"))
      (node (ref "U$1") (pin "2") (pinfunction "SDO_2") (pintype "bidirectional"))
    )
    (net (code "88") (name "SDO_PIN_2") (class "Default")
      (node (ref "SJ8") (pin "1") (pinfunction "1_1") (pintype "passive"))
      (node (ref "U$3") (pin "2") (pinfunction "SDO_2") (pintype "bidirectional"))
    )
    (net (code "89") (name "SD_2") (class "Default")
      (node (ref "J5") (pin "2") (pinfunction "2_2") (pintype "passive"))
      (node (ref "R19") (pin "1") (pinfunction "1_1") (pintype "passive"))
    )
    (net (code "90") (name "SD_PIN") (class "Default")
      (node (ref "C15") (pin "1") (pinfunction "1_1") (pintype "passive"))
      (node (ref "C41") (pin "1") (pinfunction "1_1") (pintype "passive"))
      (node (ref "J3") (pin "1") (pinfunction "1_1") (pintype "passive"))
      (node (ref "J4") (pin "1") (pinfunction "1_1") (pintype "passive"))
      (node (ref "R16") (pin "2") (pinfunction "2_2") (pintype "passive"))
      (node (ref "U$2") (pin "11") (pinfunction "/SD_11") (pintype "input"))
      (node (ref "U$5") (pin "11") (pinfunction "/SD_11") (pintype "input"))
    )
    (net (code "91") (name "SD_PIN_2") (class "Default")
      (node (ref "C66") (pin "1") (pinfunction "1_1") (pintype "passive"))
      (node (ref "C88") (pin "1") (pinfunction "1_1") (pintype "passive"))
      (node (ref "J7") (pin "1") (pinfunction "1_1") (pintype "passive"))
      (node (ref "J8") (pin "1") (pinfunction "1_1") (pintype "passive"))
      (node (ref "R19") (pin "2") (pinfunction "2_2") (pintype "passive"))
      (node (ref "U$1") (pin "11") (pinfunction "/SD_11") (pintype "input"))
      (node (ref "U$3") (pin "11") (pinfunction "/SD_11") (pintype "input"))
    )
    (net (code "92") (name "SENSE") (class "Default")
      (node (ref "C12") (pin "1") (pinfunction "1_1") (pintype "passive"))
      (node (ref "TP5") (pin "TP") (pinfunction "TP_TP") (pintype "input"))
      (node (ref "U$5") (pin "16") (pinfunction "SENSE_16") (pintype "power_in"))
    )
    (net (code "93") (name "SENSE2") (class "Default")
      (node (ref "C24") (pin "1") (pinfunction "1_1") (pintype "passive"))
      (node (ref "TP6") (pin "TP") (pinfunction "TP_TP") (pintype "input"))
      (node (ref "U$2") (pin "16") (pinfunction "SENSE_16") (pintype "power_in"))
    )
    (net (code "94") (name "SENSE2_2") (class "Default")
      (node (ref "C71") (pin "1") (pinfunction "1_1") (pintype "passive"))
      (node (ref "TP10") (pin "TP") (pinfunction "TP_TP") (pintype "input"))
      (node (ref "U$1") (pin "16") (pinfunction "SENSE_16") (pintype "power_in"))
    )
    (net (code "95") (name "SENSE_2") (class "Default")
      (node (ref "C49") (pin "1") (pinfunction "1_1") (pintype "passive"))
      (node (ref "TP9") (pin "TP") (pinfunction "TP_TP") (pintype "input"))
      (node (ref "U$3") (pin "16") (pinfunction "SENSE_16") (pintype "power_in"))
    )
    (net (code "96") (name "VCECLAMP") (class "Default")
      (node (ref "R15-D.N.M") (pin "2") (pinfunction "2_2") (pintype "passive"))
      (node (ref "R9") (pin "2") (pinfunction "2_2") (pintype "passive"))
      (node (ref "U$5") (pin "19") (pinfunction "VCECLAMP_19") (pintype "power_in"))
    )
    (net (code "97") (name "VCECLAMP2") (class "Default")
      (node (ref "R1-D.N.M.2") (pin "2") (pinfunction "2_2") (pintype "passive"))
      (node (ref "R34") (pin "2") (pinfunction "2_2") (pintype "passive"))
      (node (ref "U$2") (pin "19") (pinfunction "VCECLAMP_19") (pintype "power_in"))
    )
    (net (code "98") (name "VCECLAMP2_2") (class "Default")
      (node (ref "R1-D.N.M.1") (pin "2") (pinfunction "2_2") (pintype "passive"))
      (node (ref "R51") (pin "2") (pinfunction "2_2") (pintype "passive"))
      (node (ref "U$1") (pin "19") (pinfunction "VCECLAMP_19") (pintype "power_in"))
    )
    (net (code "99") (name "VCECLAMP_2") (class "Default")
      (node (ref "R15-D.N.M1") (pin "2") (pinfunction "2_2") (pintype "passive"))
      (node (ref "R28") (pin "2") (pinfunction "2_2") (pintype "passive"))
      (node (ref "U$3") (pin "19") (pinfunction "VCECLAMP_19") (pintype "power_in"))
    )
    (net (code "100") (name "VDD") (class "Default")
      (node (ref "C36") (pin "1") (pinfunction "1_1") (pintype "passive"))
      (node (ref "C4") (pin "1") (pinfunction "1_1") (pintype "passive"))
      (node (ref "C43") (pin "1") (pinfunction "1_1") (pintype "passive"))
      (node (ref "C61") (pin "1") (pinfunction "1_1") (pintype "passive"))
      (node (ref "C7") (pin "1") (pinfunction "1_1") (pintype "passive"))
      (node (ref "C83") (pin "1") (pinfunction "1_1") (pintype "passive"))
      (node (ref "IC1") (pin "3") (pinfunction "VO_3") (pintype "passive"))
      (node (ref "J1") (pin "12") (pinfunction "12_12") (pintype "passive"))
      (node (ref "J1") (pin "8") (pinfunction "8_8") (pintype "passive"))
      (node (ref "J5") (pin "12") (pinfunction "12_12") (pintype "passive"))
      (node (ref "J5") (pin "8") (pinfunction "8_8") (pintype "passive"))
      (node (ref "R11") (pin "2") (pinfunction "2_2") (pintype "passive"))
      (node (ref "R14") (pin "2") (pinfunction "2_2") (pintype "passive"))
      (node (ref "R25") (pin "2") (pinfunction "2_2") (pintype "passive"))
      (node (ref "R26") (pin "2") (pinfunction "2_2") (pintype "passive"))
      (node (ref "R31") (pin "2") (pinfunction "2_2") (pintype "passive"))
      (node (ref "R32") (pin "2") (pinfunction "2_2") (pintype "passive"))
      (node (ref "R48") (pin "2") (pinfunction "2_2") (pintype "passive"))
      (node (ref "R49") (pin "2") (pinfunction "2_2") (pintype "passive"))
      (node (ref "SJ10") (pin "2") (pinfunction "2_2") (pintype "passive"))
      (node (ref "SJ3") (pin "2") (pinfunction "2_2") (pintype "passive"))
      (node (ref "SJ4") (pin "2") (pinfunction "2_2") (pintype "passive"))
      (node (ref "SJ6") (pin "2") (pinfunction "2_2") (pintype "passive"))
      (node (ref "U$1") (pin "7") (pinfunction "VDD_7") (pintype "power_in"))
      (node (ref "U$2") (pin "7") (pinfunction "VDD_7") (pintype "power_in"))
      (node (ref "U$3") (pin "7") (pinfunction "VDD_7") (pintype "power_in"))
      (node (ref "U$5") (pin "7") (pinfunction "VDD_7") (pintype "power_in"))
      (node (ref "U1") (pin "1") (pinfunction "+VIN_1") (pintype "bidirectional"))
      (node (ref "U2") (pin "1") (pinfunction "+VIN_1") (pintype "bidirectional"))
      (node (ref "U3") (pin "1") (pinfunction "+VIN_1") (pintype "bidirectional"))
      (node (ref "U4") (pin "1") (pinfunction "+VIN_1") (pintype "bidirectional"))
    )
    (net (code "101") (name "VH") (class "Default")
      (node (ref "C10") (pin "1") (pinfunction "1_1") (pintype "passive"))
      (node (ref "C18") (pin "1") (pinfunction "1_1") (pintype "passive"))
      (node (ref "C2") (pin "1") (pinfunction "1_1") (pintype "passive"))
      (node (ref "D1") (pin "2") (pinfunction "K_2") (pintype "bidirectional"))
      (node (ref "U$5") (pin "17") (pinfunction "VH_17") (pintype "power_in"))
      (node (ref "U2") (pin "7") (pinfunction "+VOUT_7") (pintype "bidirectional"))
    )
    (net (code "102") (name "VH2") (class "Default")
      (node (ref "C29") (pin "1") (pinfunction "1_1") (pintype "passive"))
      (node (ref "C31") (pin "1") (pinfunction "1_1") (pintype "passive"))
      (node (ref "C32") (pin "1") (pinfunction "1_1") (pintype "passive"))
      (node (ref "D7") (pin "2") (pinfunction "K_2") (pintype "bidirectional"))
      (node (ref "U$2") (pin "17") (pinfunction "VH_17") (pintype "power_in"))
      (node (ref "U3") (pin "7") (pinfunction "+VOUT_7") (pintype "bidirectional"))
    )
    (net (code "103") (name "VH2_2") (class "Default")
      (node (ref "C76") (pin "1") (pinfunction "1_1") (pintype "passive"))
      (node (ref "C78") (pin "1") (pinfunction "1_1") (pintype "passive"))
      (node (ref "C79") (pin "1") (pinfunction "1_1") (pintype "passive"))
      (node (ref "D15") (pin "2") (pinfunction "K_2") (pintype "bidirectional"))
      (node (ref "U$1") (pin "17") (pinfunction "VH_17") (pintype "power_in"))
      (node (ref "U4") (pin "7") (pinfunction "+VOUT_7") (pintype "bidirectional"))
    )
    (net (code "104") (name "VH_2") (class "Default")
      (node (ref "C54") (pin "1") (pinfunction "1_1") (pintype "passive"))
      (node (ref "C56") (pin "1") (pinfunction "1_1") (pintype "passive"))
      (node (ref "C57") (pin "1") (pinfunction "1_1") (pintype "passive"))
      (node (ref "D11") (pin "2") (pinfunction "K_2") (pintype "bidirectional"))
      (node (ref "U$3") (pin "17") (pinfunction "VH_17") (pintype "power_in"))
      (node (ref "U1") (pin "7") (pinfunction "+VOUT_7") (pintype "bidirectional"))
    )
    (net (code "105") (name "VL") (class "Default")
      (node (ref "C1") (pin "1") (pinfunction "1_1") (pintype "passive"))
      (node (ref "C16") (pin "1") (pinfunction "1_1") (pintype "passive"))
      (node (ref "C17") (pin "1") (pinfunction "1_1") (pintype "passive"))
      (node (ref "C3") (pin "1") (pinfunction "1_1") (pintype "passive"))
      (node (ref "D1") (pin "1") (pinfunction "A_1") (pintype "bidirectional"))
      (node (ref "R7") (pin "2") (pinfunction "2_2") (pintype "passive"))
      (node (ref "R9") (pin "1") (pinfunction "1_1") (pintype "passive"))
      (node (ref "U$5") (pin "14") (pinfunction "VL_14") (pintype "power_in"))
      (node (ref "U$5") (pin "23") (pinfunction "VL_23") (pintype "power_in"))
      (node (ref "U2") (pin "5") (pinfunction "-VOUT_5") (pintype "bidirectional"))
    )
    (net (code "106") (name "VL2") (class "Default")
      (node (ref "C27") (pin "1") (pinfunction "1_1") (pintype "passive"))
      (node (ref "C28") (pin "1") (pinfunction "1_1") (pintype "passive"))
      (node (ref "C30") (pin "1") (pinfunction "1_1") (pintype "passive"))
      (node (ref "C33") (pin "1") (pinfunction "1_1") (pintype "passive"))
      (node (ref "D7") (pin "1") (pinfunction "A_1") (pintype "bidirectional"))
      (node (ref "R23") (pin "2") (pinfunction "2_2") (pintype "passive"))
      (node (ref "R34") (pin "1") (pinfunction "1_1") (pintype "passive"))
      (node (ref "U$2") (pin "14") (pinfunction "VL_14") (pintype "power_in"))
      (node (ref "U$2") (pin "23") (pinfunction "VL_23") (pintype "power_in"))
      (node (ref "U3") (pin "5") (pinfunction "-VOUT_5") (pintype "bidirectional"))
    )
    (net (code "107") (name "VL2_2") (class "Default")
      (node (ref "C74") (pin "1") (pinfunction "1_1") (pintype "passive"))
      (node (ref "C75") (pin "1") (pinfunction "1_1") (pintype "passive"))
      (node (ref "C77") (pin "1") (pinfunction "1_1") (pintype "passive"))
      (node (ref "C80") (pin "1") (pinfunction "1_1") (pintype "passive"))
      (node (ref "D15") (pin "1") (pinfunction "A_1") (pintype "bidirectional"))
      (node (ref "R46") (pin "2") (pinfunction "2_2") (pintype "passive"))
      (node (ref "R51") (pin "1") (pinfunction "1_1") (pintype "passive"))
      (node (ref "U$1") (pin "14") (pinfunction "VL_14") (pintype "power_in"))
      (node (ref "U$1") (pin "23") (pinfunction "VL_23") (pintype "power_in"))
      (node (ref "U4") (pin "5") (pinfunction "-VOUT_5") (pintype "bidirectional"))
    )
    (net (code "108") (name "VL_2") (class "Default")
      (node (ref "C52") (pin "1") (pinfunction "1_1") (pintype "passive"))
      (node (ref "C53") (pin "1") (pinfunction "1_1") (pintype "passive"))
      (node (ref "C55") (pin "1") (pinfunction "1_1") (pintype "passive"))
      (node (ref "C58") (pin "1") (pinfunction "1_1") (pintype "passive"))
      (node (ref "D11") (pin "1") (pinfunction "A_1") (pintype "bidirectional"))
      (node (ref "R18") (pin "2") (pinfunction "2_2") (pintype "passive"))
      (node (ref "R28") (pin "1") (pinfunction "1_1") (pintype "passive"))
      (node (ref "U$3") (pin "14") (pinfunction "VL_14") (pintype "power_in"))
      (node (ref "U$3") (pin "23") (pinfunction "VL_23") (pintype "power_in"))
      (node (ref "U1") (pin "5") (pinfunction "-VOUT_5") (pintype "bidirectional"))
    )
    (net (code "109") (name "VREG") (class "Default")
      (node (ref "C19") (pin "1") (pinfunction "1_1") (pintype "passive"))
      (node (ref "C34") (pin "1") (pinfunction "1_1") (pintype "passive"))
      (node (ref "C35") (pin "1") (pinfunction "1_1") (pintype "passive"))
      (node (ref "C5") (pin "1") (pinfunction "1_1") (pintype "passive"))
      (node (ref "SJ3") (pin "1") (pinfunction "1_1") (pintype "passive"))
      (node (ref "SJ6") (pin "1") (pinfunction "1_1") (pintype "passive"))
      (node (ref "U$2") (pin "6") (pinfunction "VREG_6") (pintype "power_in"))
      (node (ref "U$5") (pin "6") (pinfunction "VREG_6") (pintype "power_in"))
    )
    (net (code "110") (name "VREGISO") (class "Default")
      (node (ref "C11") (pin "1") (pinfunction "1_1") (pintype "passive"))
      (node (ref "C14") (pin "1") (pinfunction "1_1") (pintype "passive"))
      (node (ref "U$5") (pin "15") (pinfunction "VREGISO_15") (pintype "power_in"))
    )
    (net (code "111") (name "VREGISO2") (class "Default")
      (node (ref "C25") (pin "1") (pinfunction "1_1") (pintype "passive"))
      (node (ref "C26") (pin "1") (pinfunction "1_1") (pintype "passive"))
      (node (ref "U$2") (pin "15") (pinfunction "VREGISO_15") (pintype "power_in"))
    )
    (net (code "112") (name "VREGISO2_2") (class "Default")
      (node (ref "C72") (pin "1") (pinfunction "1_1") (pintype "passive"))
      (node (ref "C73") (pin "1") (pinfunction "1_1") (pintype "passive"))
      (node (ref "U$1") (pin "15") (pinfunction "VREGISO_15") (pintype "power_in"))
    )
    (net (code "113") (name "VREGISO_2") (class "Default")
      (node (ref "C50") (pin "1") (pinfunction "1_1") (pintype "passive"))
      (node (ref "C51") (pin "1") (pinfunction "1_1") (pintype "passive"))
      (node (ref "U$3") (pin "15") (pinfunction "VREGISO_15") (pintype "power_in"))
    )
    (net (code "114") (name "VREG_2") (class "Default")
      (node (ref "C59") (pin "1") (pinfunction "1_1") (pintype "passive"))
      (node (ref "C60") (pin "1") (pinfunction "1_1") (pintype "passive"))
      (node (ref "C81") (pin "1") (pinfunction "1_1") (pintype "passive"))
      (node (ref "C82") (pin "1") (pinfunction "1_1") (pintype "passive"))
      (node (ref "SJ10") (pin "1") (pinfunction "1_1") (pintype "passive"))
      (node (ref "SJ4") (pin "1") (pinfunction "1_1") (pintype "passive"))
      (node (ref "U$1") (pin "6") (pinfunction "VREG_6") (pintype "power_in"))
      (node (ref "U$3") (pin "6") (pinfunction "VREG_6") (pintype "power_in"))
    )
    (net (code "115") (name "unconnected-(J1-Pad6)") (class "Default")
      (node (ref "J1") (pin "6") (pinfunction "6_6") (pintype "passive"))
    )
    (net (code "116") (name "unconnected-(J1-Pad7)") (class "Default")
      (node (ref "J1") (pin "7") (pinfunction "7_7") (pintype "passive"))
    )
    (net (code "117") (name "unconnected-(J5-Pad6)") (class "Default")
      (node (ref "J5") (pin "6") (pinfunction "6_6") (pintype "passive"))
    )
    (net (code "118") (name "unconnected-(J5-Pad7)") (class "Default")
      (node (ref "J5") (pin "7") (pinfunction "7_7") (pintype "passive"))
    )
    (net (code "119") (name "unconnected-(X1-B-1-PadB1)") (class "Default")
      (node (ref "X1") (pin "B1") (pinfunction "B-1_B1") (pintype "passive"))
    )
    (net (code "120") (name "unconnected-(X1-B-2-PadB2)") (class "Default")
      (node (ref "X1") (pin "B2") (pinfunction "B-2_B2") (pintype "passive"))
    )
    (net (code "121") (name "unconnected-(X2-B-1-PadB1)") (class "Default")
      (node (ref "X2") (pin "B1") (pinfunction "B-1_B1") (pintype "passive"))
    )
    (net (code "122") (name "unconnected-(X2-B-2-PadB2)") (class "Default")
      (node (ref "X2") (pin "B2") (pinfunction "B-2_B2") (pintype "passive"))
    )
    (net (code "123") (name "unconnected-(X3-B-1-PadB1)") (class "Default")
      (node (ref "X3") (pin "B1") (pinfunction "B-1_B1") (pintype "passive"))
    )
    (net (code "124") (name "unconnected-(X3-B-2-PadB2)") (class "Default")
      (node (ref "X3") (pin "B2") (pinfunction "B-2_B2") (pintype "passive"))
    )
    (net (code "125") (name "unconnected-(X4-B-1-PadB1)") (class "Default")
      (node (ref "X4") (pin "B1") (pinfunction "B-1_B1") (pintype "passive"))
    )
    (net (code "126") (name "unconnected-(X4-B-2-PadB2)") (class "Default")
      (node (ref "X4") (pin "B2") (pinfunction "B-2_B2") (pintype "passive"))
    )
    (net (code "127") (name "unconnected-(X5-B-1-PadB1)") (class "Default")
      (node (ref "X5") (pin "B1") (pinfunction "B-1_B1") (pintype "passive"))
    )
    (net (code "128") (name "unconnected-(X5-B-2-PadB2)") (class "Default")
      (node (ref "X5") (pin "B2") (pinfunction "B-2_B2") (pintype "passive"))
    )
    (net (code "129") (name "unconnected-(X6-B-1-PadB1)") (class "Default")
      (node (ref "X6") (pin "B1") (pinfunction "B-1_B1") (pintype "passive"))
    )
    (net (code "130") (name "unconnected-(X6-B-2-PadB2)") (class "Default")
      (node (ref "X6") (pin "B2") (pinfunction "B-2_B2") (pintype "passive"))
    )
    (net (code "131") (name "{slash}DIAG1") (class "Default")
      (node (ref "DL2") (pin "C") (pinfunction "C_C") (pintype "passive"))
      (node (ref "J1") (pin "3") (pinfunction "3_3") (pintype "passive"))
      (node (ref "U$5") (pin "10") (pinfunction "/DIAG1_10") (pintype "output"))
    )
    (net (code "132") (name "{slash}DIAG1_2") (class "Default")
      (node (ref "DL6") (pin "C") (pinfunction "C_C") (pintype "passive"))
      (node (ref "J5") (pin "3") (pinfunction "3_3") (pintype "passive"))
      (node (ref "U$3") (pin "10") (pinfunction "/DIAG1_10") (pintype "output"))
    )
    (net (code "133") (name "{slash}DIAG12") (class "Default")
      (node (ref "DL4") (pin "C") (pinfunction "C_C") (pintype "passive"))
      (node (ref "J2") (pin "2") (pinfunction "2_2") (pintype "passive"))
      (node (ref "U$2") (pin "10") (pinfunction "/DIAG1_10") (pintype "output"))
    )
    (net (code "134") (name "{slash}DIAG12_2") (class "Default")
      (node (ref "DL8") (pin "C") (pinfunction "C_C") (pintype "passive"))
      (node (ref "J6") (pin "2") (pinfunction "2_2") (pintype "passive"))
      (node (ref "U$1") (pin "10") (pinfunction "/DIAG1_10") (pintype "output"))
    )
  )
)
